# axiom_beta_plugin_module_TE0714_SDI_v0_4.net
KiCad netlist of a schematic drawn in EAGLE
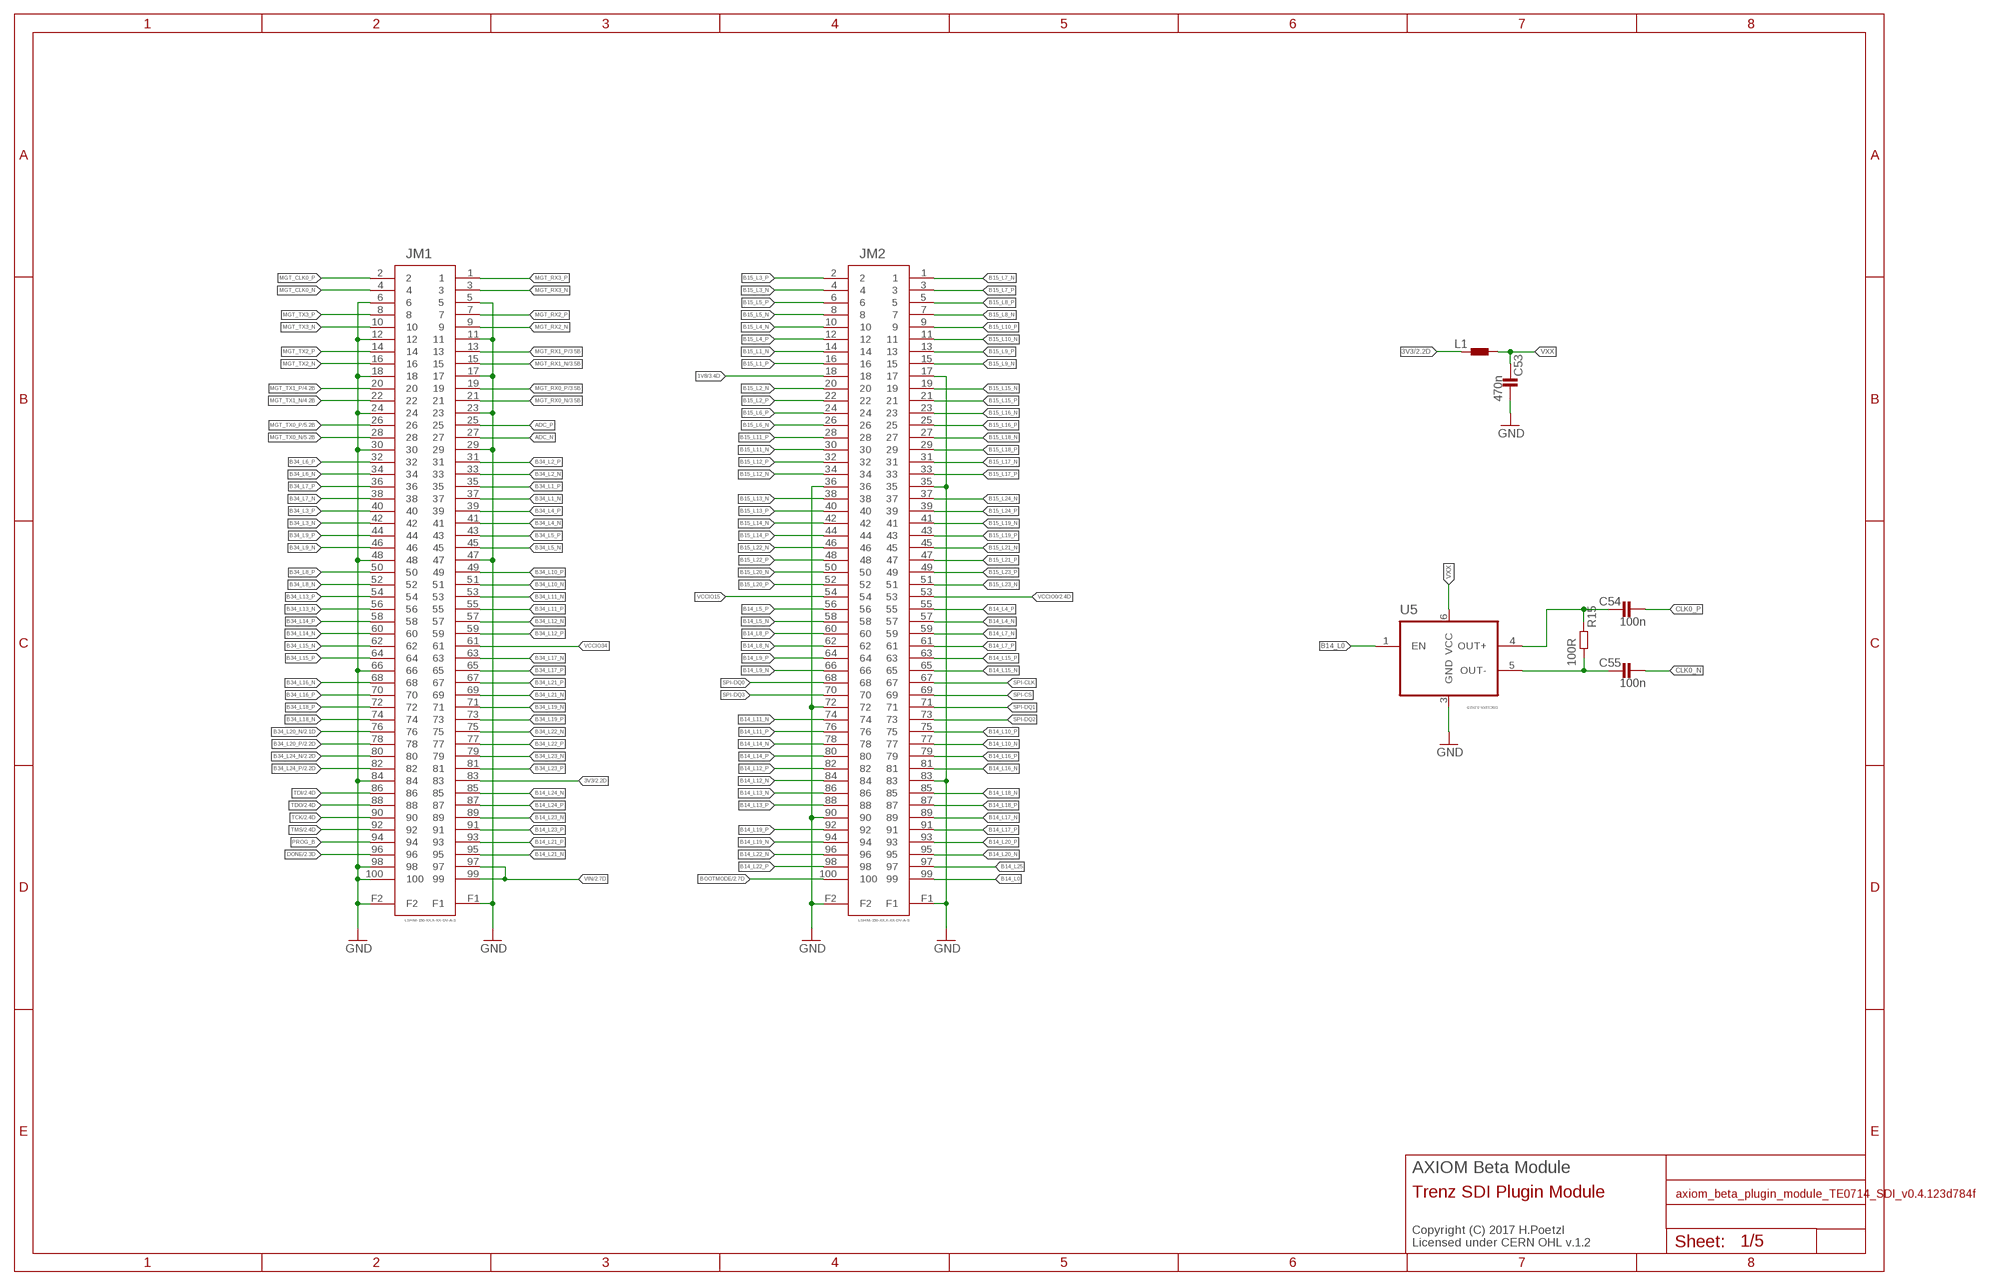
[diagram p0: schematic, sheet 1]
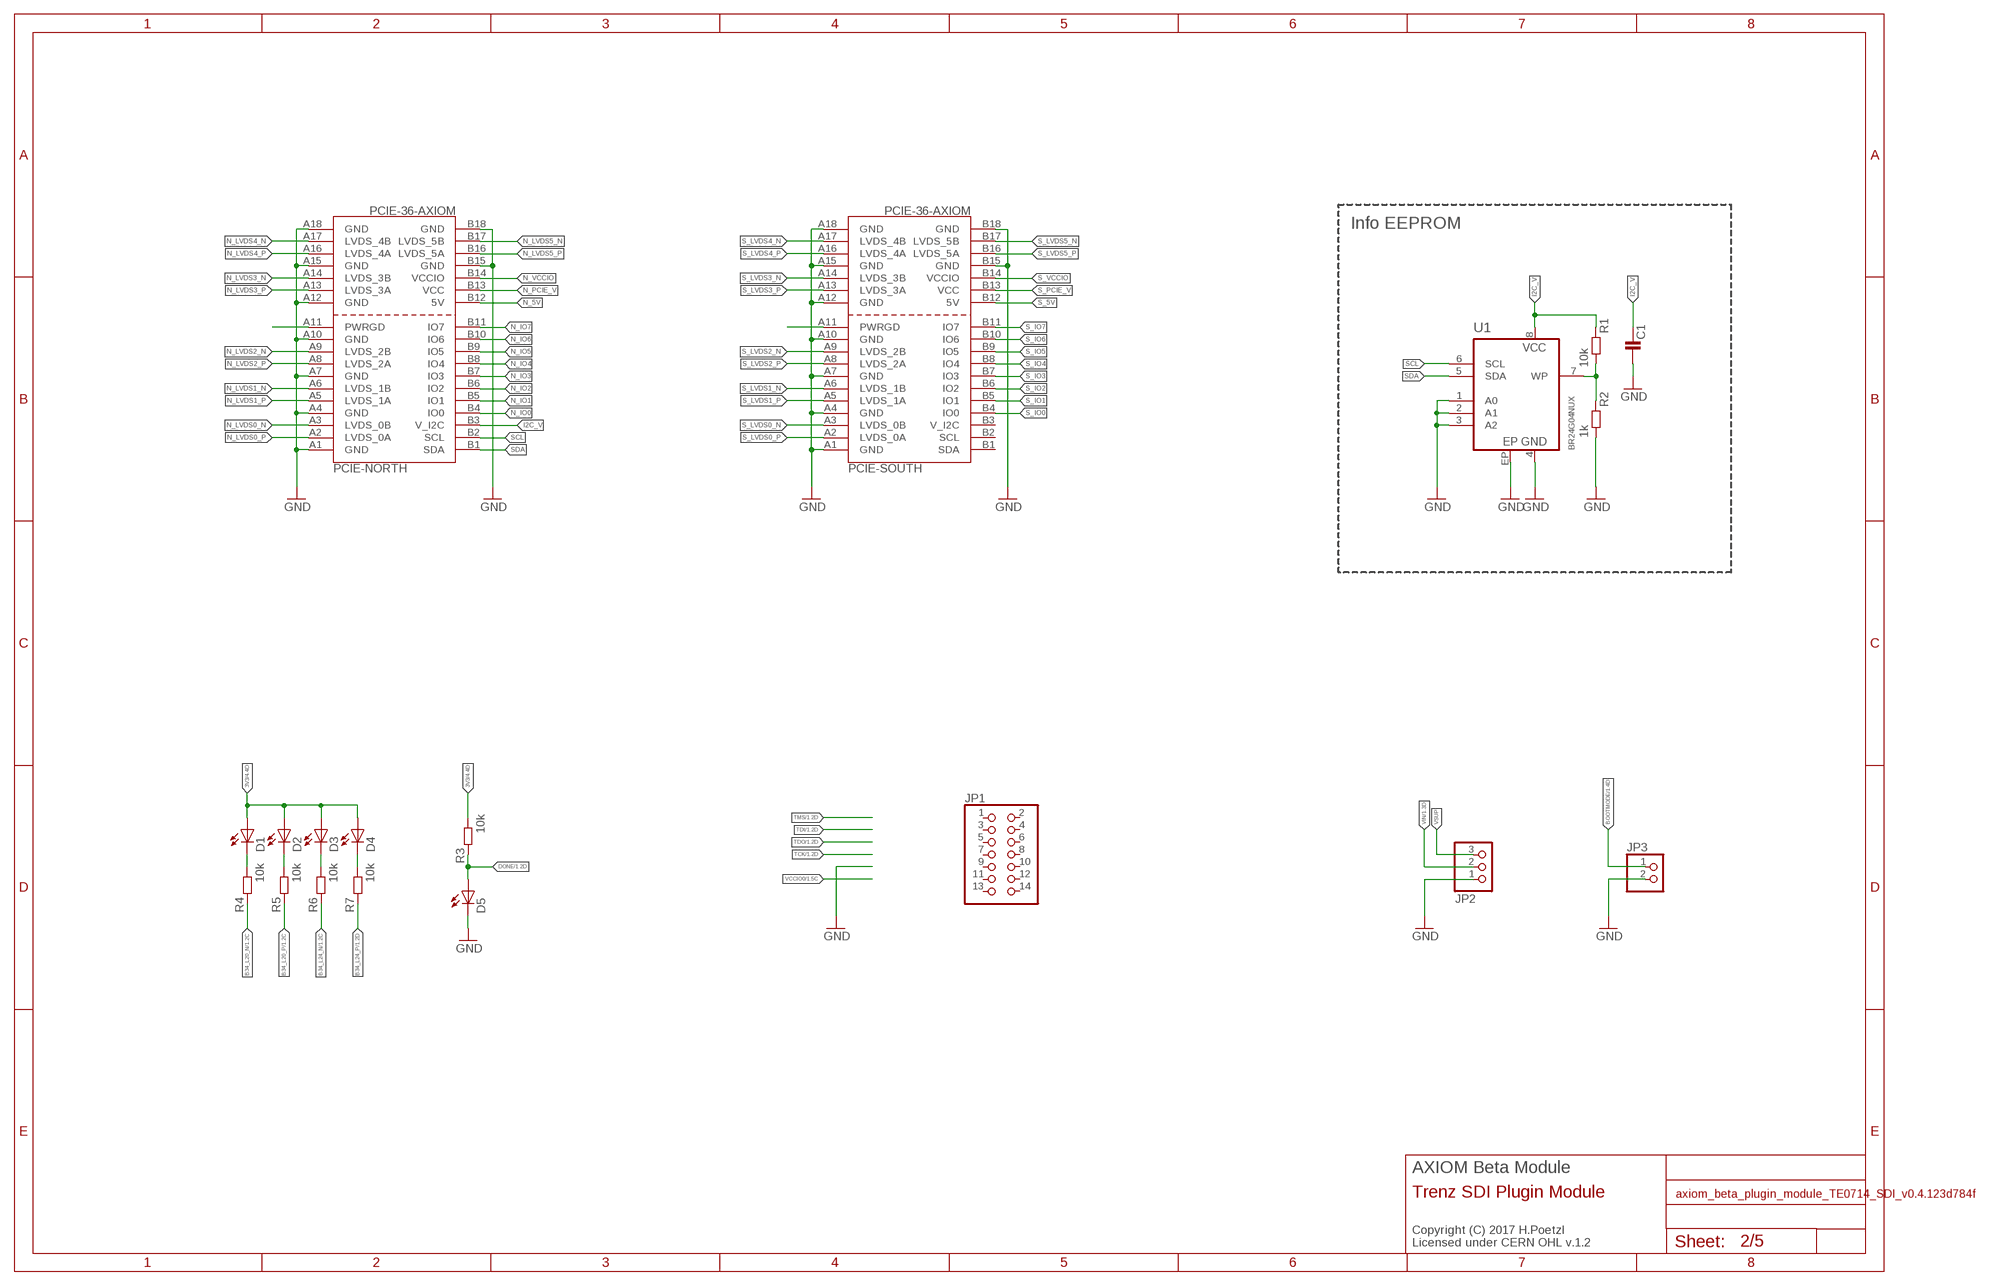
[diagram p1: schematic, sheet 2]
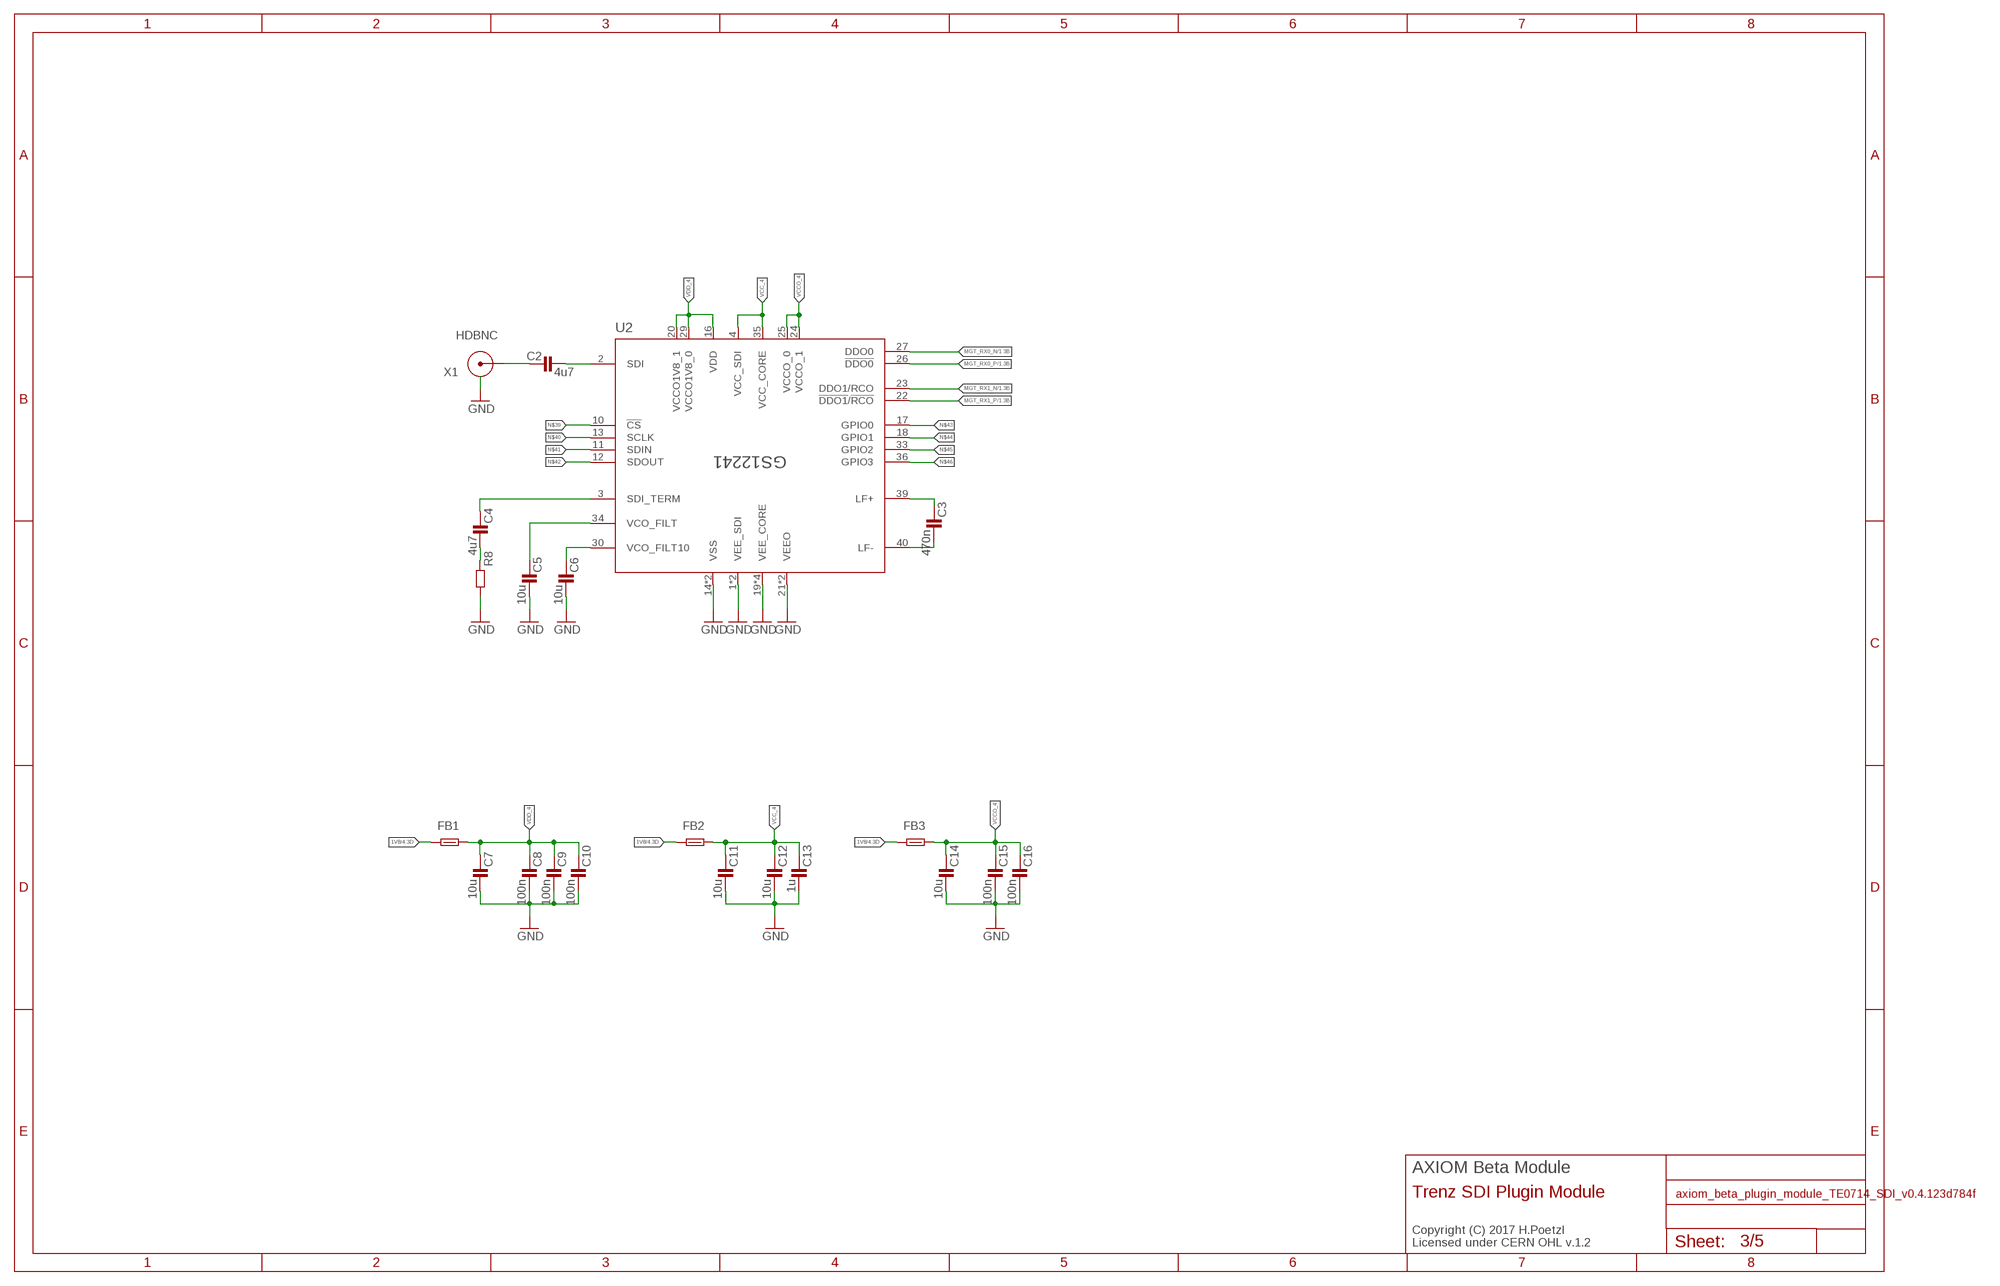
[diagram p2: schematic, sheet 3]
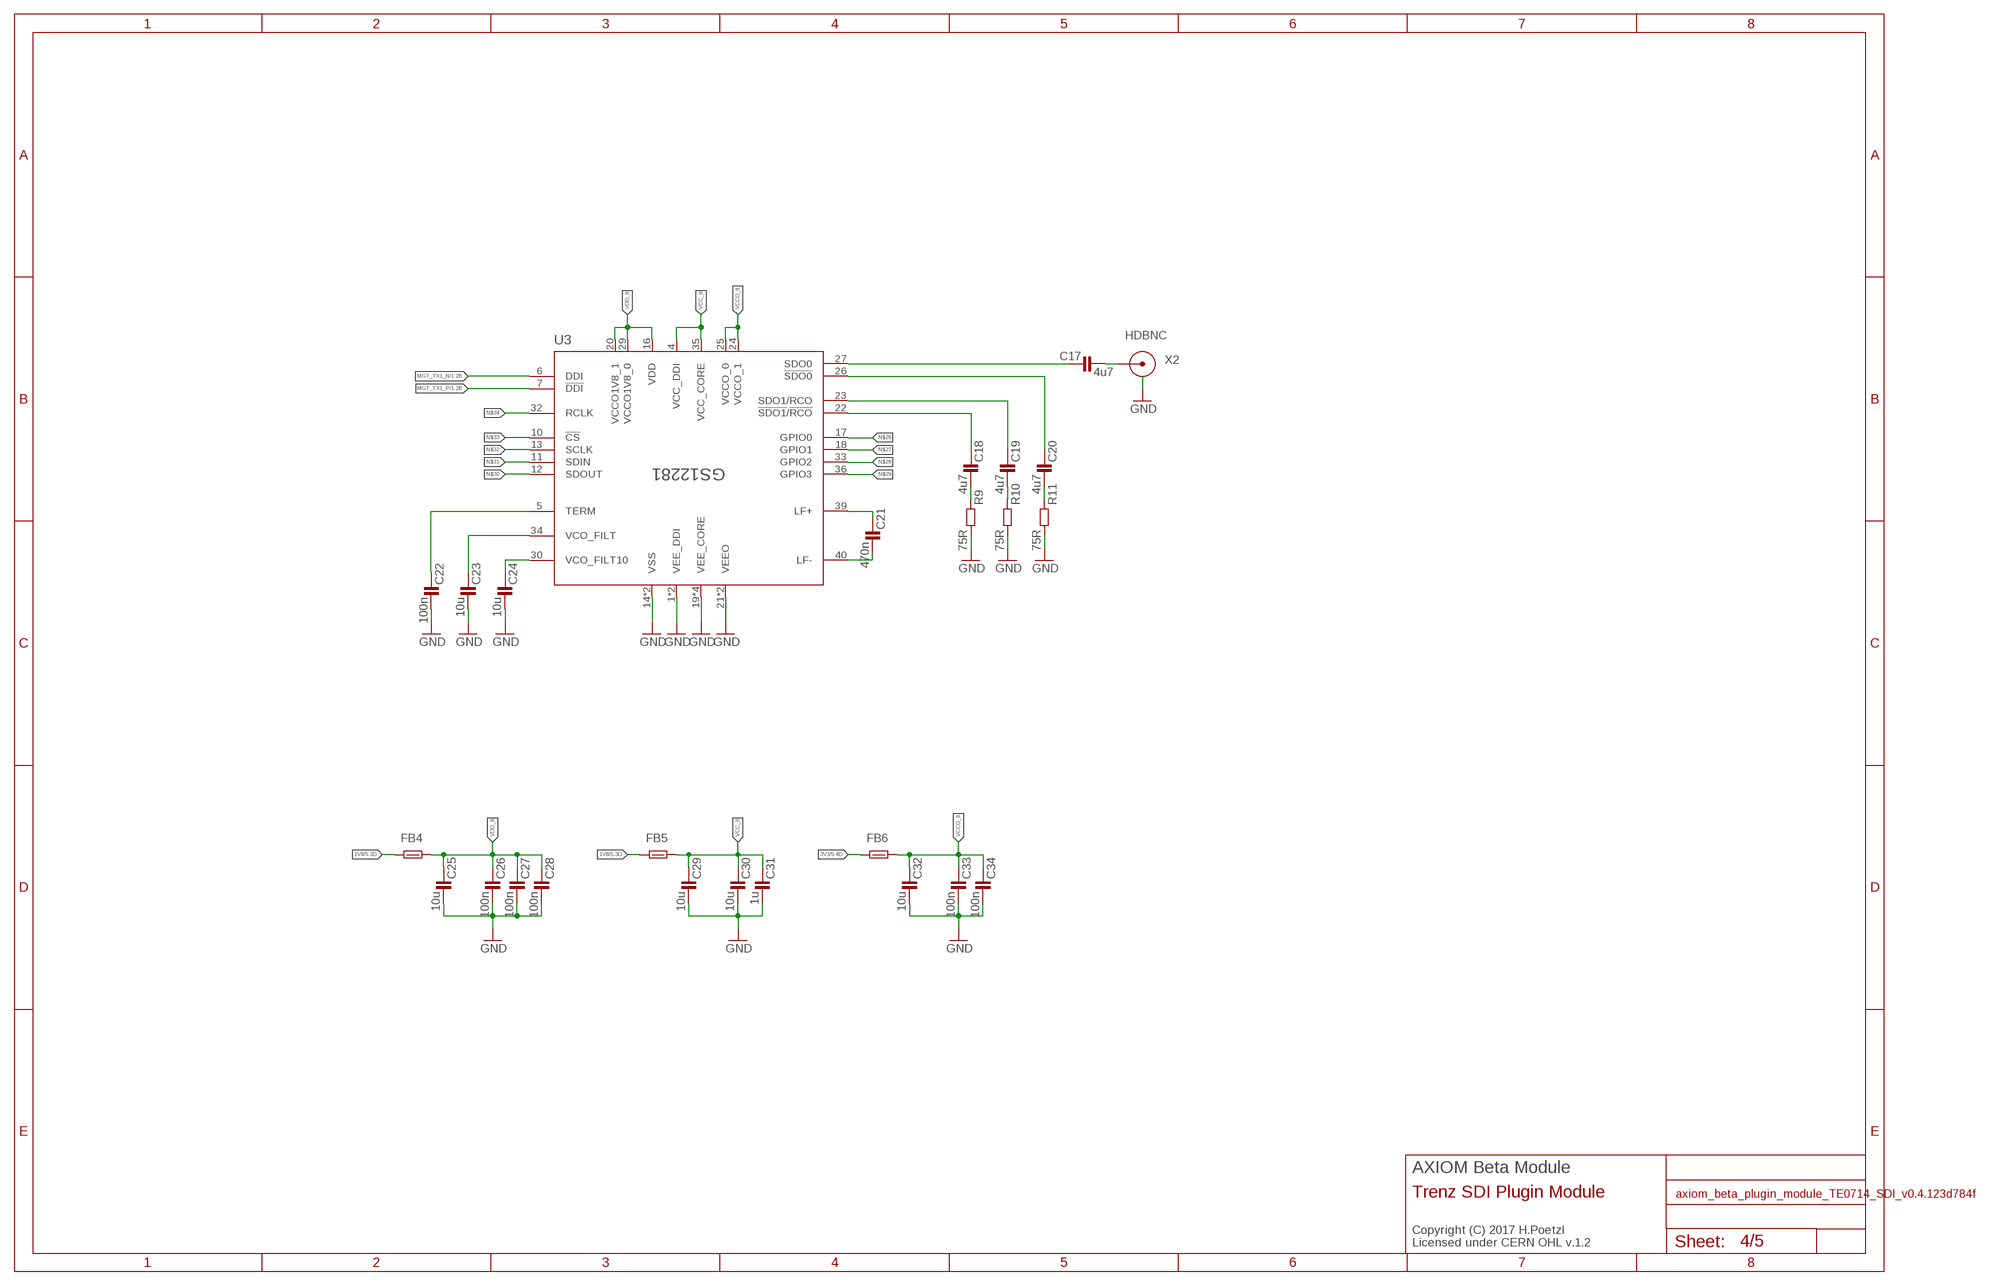
[diagram p3: schematic, sheet 4]
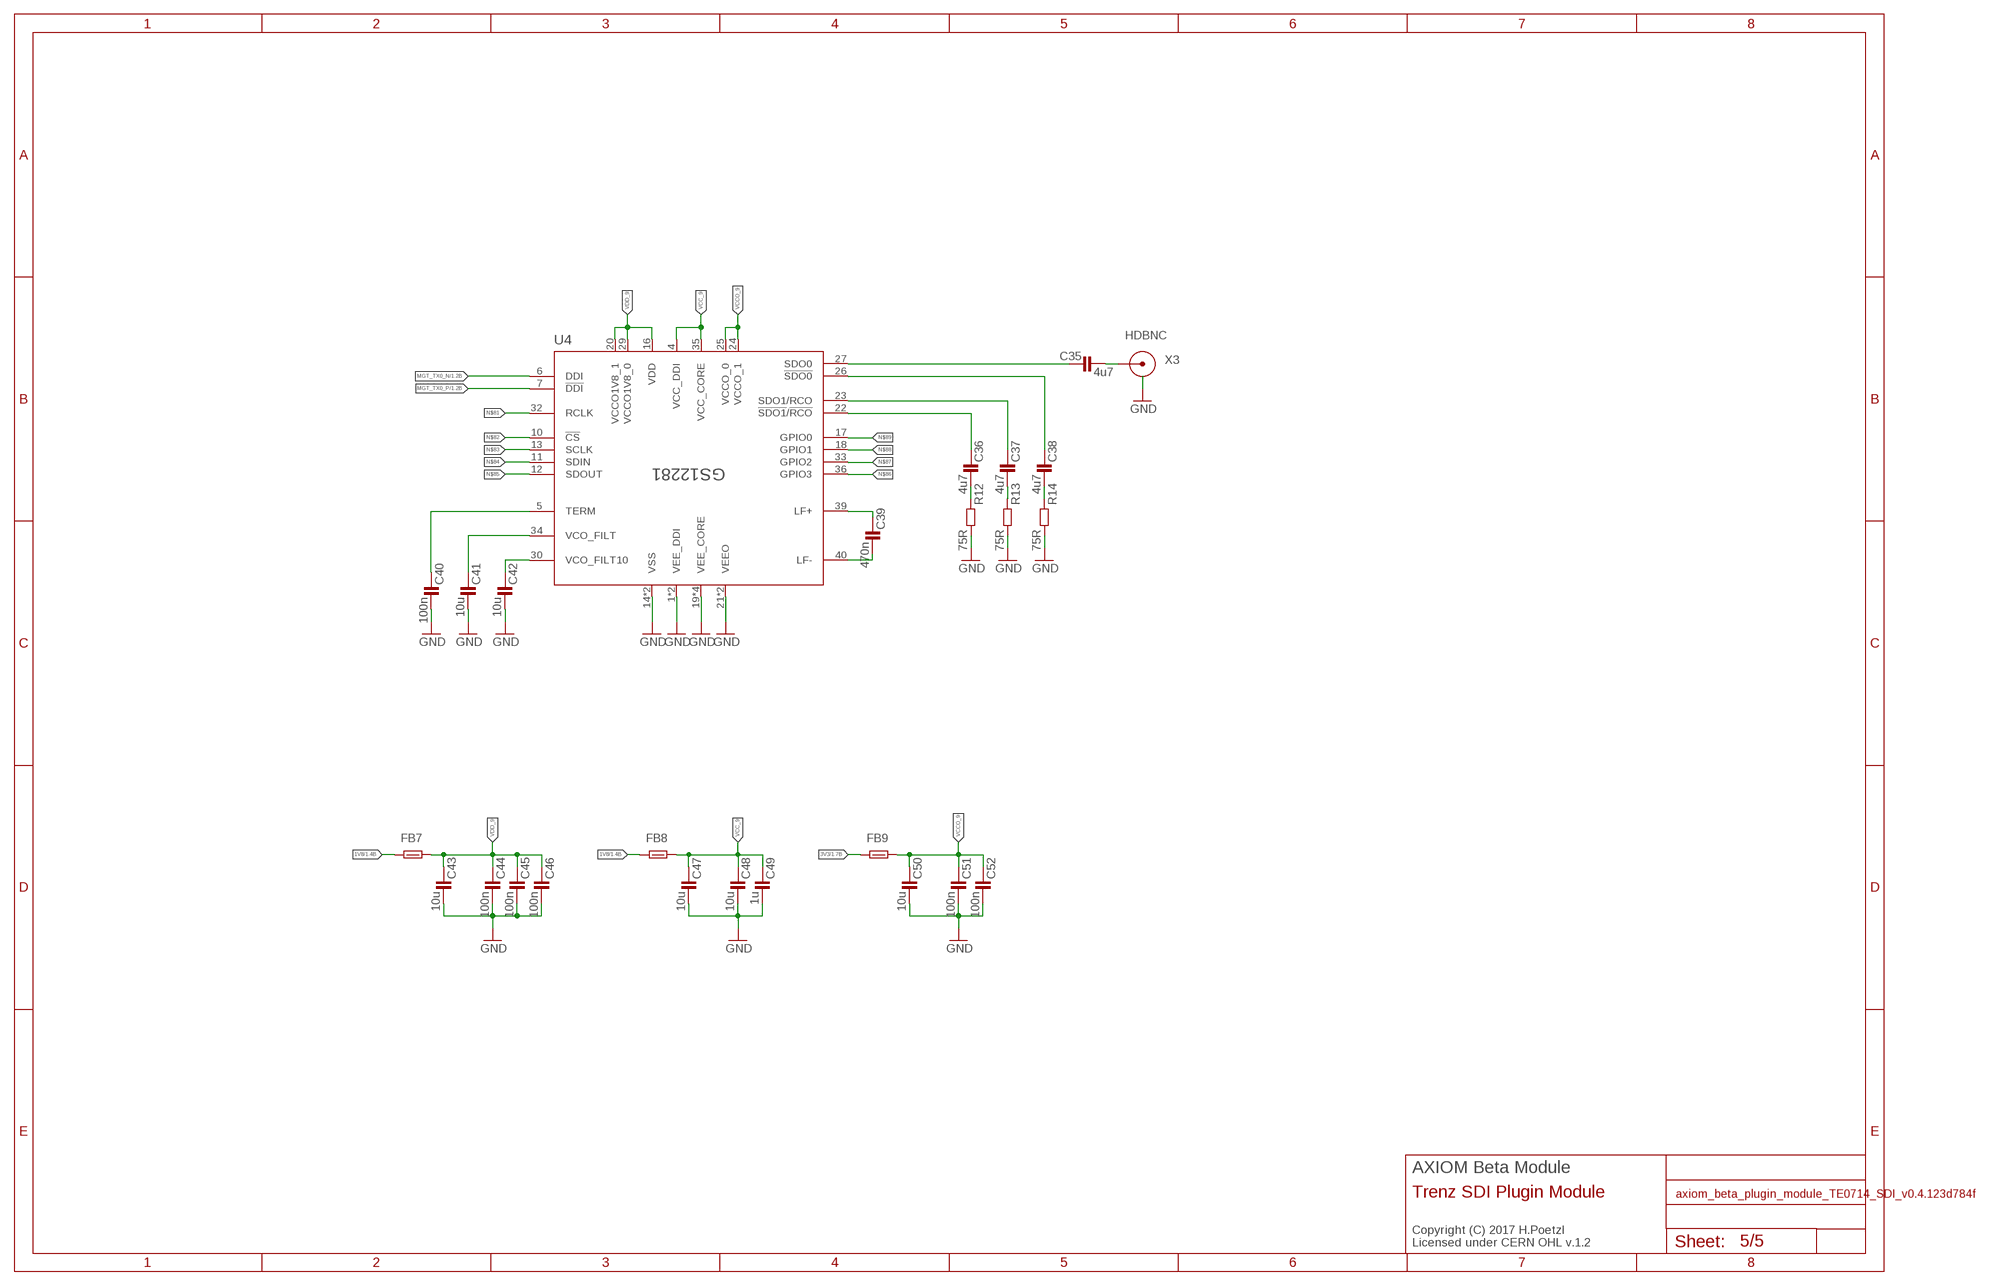
[diagram p4: schematic, sheet 5]

(export (version "E")
  (design (tool "Eeschema 10.0.6"))
  (components
    (comp (ref "C17")
      (value "4u7")
      (footprint "eagle-import:0402-C")
      (libsource (lib "eagle-import") (part "C0402-C"))
    )
    (comp (ref "C18")
      (value "4u7")
      (footprint "eagle-import:0201-C")
      (libsource (lib "eagle-import") (part "C0201-C"))
    )
    (comp (ref "C19")
      (value "4u7")
      (footprint "eagle-import:0201-C")
      (libsource (lib "eagle-import") (part "C0201-C"))
    )
    (comp (ref "C20")
      (value "4u7")
      (footprint "eagle-import:0201-C")
      (libsource (lib "eagle-import") (part "C0201-C"))
    )
    (comp (ref "C21")
      (value "470n")
      (footprint "eagle-import:0201-C")
      (libsource (lib "eagle-import") (part "C0201-C"))
    )
    (comp (ref "C22")
      (value "100n")
      (footprint "eagle-import:0201-C")
      (libsource (lib "eagle-import") (part "C0201-C"))
    )
    (comp (ref "C23")
      (value "10u")
      (footprint "eagle-import:0201-C")
      (libsource (lib "eagle-import") (part "C0201-C"))
    )
    (comp (ref "C24")
      (value "10u")
      (footprint "eagle-import:0201-C")
      (libsource (lib "eagle-import") (part "C0201-C"))
    )
    (comp (ref "C25")
      (value "10u")
      (footprint "eagle-import:0402-C")
      (libsource (lib "eagle-import") (part "C0402-C"))
    )
    (comp (ref "C26")
      (value "100n")
      (footprint "eagle-import:0201-C")
      (libsource (lib "eagle-import") (part "C0201-C"))
    )
    (comp (ref "C27")
      (value "100n")
      (footprint "eagle-import:0201-C")
      (libsource (lib "eagle-import") (part "C0201-C"))
    )
    (comp (ref "C28")
      (value "100n")
      (footprint "eagle-import:0201-C")
      (libsource (lib "eagle-import") (part "C0201-C"))
    )
    (comp (ref "C29")
      (value "10u")
      (footprint "eagle-import:0402-C")
      (libsource (lib "eagle-import") (part "C0402-C"))
    )
    (comp (ref "C30")
      (value "10u")
      (footprint "eagle-import:0201-C")
      (libsource (lib "eagle-import") (part "C0201-C"))
    )
    (comp (ref "C31")
      (value "1u")
      (footprint "eagle-import:0201-C")
      (libsource (lib "eagle-import") (part "C0201-C"))
    )
    (comp (ref "C32")
      (value "10u")
      (footprint "eagle-import:0402-C")
      (libsource (lib "eagle-import") (part "C0402-C"))
    )
    (comp (ref "C33")
      (value "100n")
      (footprint "eagle-import:0201-C")
      (libsource (lib "eagle-import") (part "C0201-C"))
    )
    (comp (ref "C34")
      (value "100n")
      (footprint "eagle-import:0201-C")
      (libsource (lib "eagle-import") (part "C0201-C"))
    )
    (comp (ref "FB4")
      (value "FB0402-C")
      (footprint "eagle-import:0402-C")
      (libsource (lib "eagle-import") (part "FB0402-C"))
    )
    (comp (ref "FB5")
      (value "FB0402-C")
      (footprint "eagle-import:0402-C")
      (libsource (lib "eagle-import") (part "FB0402-C"))
    )
    (comp (ref "FB6")
      (value "FB0402-C")
      (footprint "eagle-import:0402-C")
      (libsource (lib "eagle-import") (part "FB0402-C"))
    )
    (comp (ref "R9")
      (value "75R")
      (footprint "eagle-import:0201-C")
      (libsource (lib "eagle-import") (part "R0201-C"))
    )
    (comp (ref "R10")
      (value "75R")
      (footprint "eagle-import:0201-C")
      (libsource (lib "eagle-import") (part "R0201-C"))
    )
    (comp (ref "R11")
      (value "75R")
      (footprint "eagle-import:0201-C")
      (libsource (lib "eagle-import") (part "R0201-C"))
    )
    (comp (ref "U3")
      (value "GS12281")
      (footprint "eagle-import:UQFN40P600X400X100-41N")
      (libsource (lib "eagle-import") (part "GS12281"))
    )
    (comp (ref "X2")
      (value "HDBNC")
      (footprint "eagle-import:HDBNC_EDGE_2SIDE")
      (libsource (lib "eagle-import") (part "HDBNC"))
    )
    (comp (ref "C1")
      (value "C0402-B")
      (footprint "eagle-import:0402-B")
      (libsource (lib "eagle-import") (part "C0402-B"))
    )
    (comp (ref "D1")
      (value "LED")
      (footprint "eagle-import:SMARTLED-TTW")
      (libsource (lib "eagle-import") (part "LED"))
    )
    (comp (ref "D2")
      (value "LED")
      (footprint "eagle-import:SMARTLED-TTW")
      (libsource (lib "eagle-import") (part "LED"))
    )
    (comp (ref "D3")
      (value "LED")
      (footprint "eagle-import:SMARTLED-TTW")
      (libsource (lib "eagle-import") (part "LED"))
    )
    (comp (ref "D4")
      (value "LED")
      (footprint "eagle-import:SMARTLED-TTW")
      (libsource (lib "eagle-import") (part "LED"))
    )
    (comp (ref "D5")
      (value "LED")
      (footprint "eagle-import:SMARTLED-TTW")
      (libsource (lib "eagle-import") (part "LED"))
    )
    (comp (ref "JP1")
      (value "PINHD-2X07_2.00")
      (footprint "eagle-import:2X07M")
      (libsource (lib "eagle-import") (part "PINHD-2X07_2.00"))
    )
    (comp (ref "JP2")
      (value "PINHD-1X03_2.54-90°-S")
      (footprint "eagle-import:1X03_90-S")
      (libsource (lib "eagle-import") (part "PINHD-1X03_2.54-90°-S"))
    )
    (comp (ref "JP3")
      (value "PINHD-1X02_2.54-S")
      (footprint "eagle-import:1X02-S")
      (libsource (lib "eagle-import") (part "PINHD-1X02_2.54-S"))
    )
    (comp (ref "PCIE-NORTH")
      (value "PCIE-36-AXIOM")
      (footprint "eagle-import:PCIE-36-AXIOM")
      (libsource (lib "eagle-import") (part "PCIE-36-AXIOM"))
    )
    (comp (ref "PCIE-SOUTH")
      (value "PCIE-36-AXIOM")
      (footprint "eagle-import:PCIE-36-AXIOM")
      (libsource (lib "eagle-import") (part "PCIE-36-AXIOM"))
    )
    (comp (ref "R1")
      (value "10k")
      (footprint "eagle-import:0402-B")
      (libsource (lib "eagle-import") (part "R0402-B"))
    )
    (comp (ref "R2")
      (value "1k")
      (footprint "eagle-import:0402-B")
      (libsource (lib "eagle-import") (part "R0402-B"))
    )
    (comp (ref "R3")
      (value "10k")
      (footprint "eagle-import:0402-C")
      (libsource (lib "eagle-import") (part "R0402-C"))
    )
    (comp (ref "R4")
      (value "10k")
      (footprint "eagle-import:0402-C")
      (libsource (lib "eagle-import") (part "R0402-C"))
    )
    (comp (ref "R5")
      (value "10k")
      (footprint "eagle-import:0402-C")
      (libsource (lib "eagle-import") (part "R0402-C"))
    )
    (comp (ref "R6")
      (value "10k")
      (footprint "eagle-import:0402-C")
      (libsource (lib "eagle-import") (part "R0402-C"))
    )
    (comp (ref "R7")
      (value "10k")
      (footprint "eagle-import:0402-C")
      (libsource (lib "eagle-import") (part "R0402-C"))
    )
    (comp (ref "U1")
      (value "BR24G04NUX")
      (footprint "eagle-import:DFN200X300X100-9N")
      (libsource (lib "eagle-import") (part "BR24G04NUX"))
    )
    (comp (ref "C35")
      (value "4u7")
      (footprint "eagle-import:0402-C")
      (libsource (lib "eagle-import") (part "C0402-C"))
    )
    (comp (ref "C36")
      (value "4u7")
      (footprint "eagle-import:0201-C")
      (libsource (lib "eagle-import") (part "C0201-C"))
    )
    (comp (ref "C37")
      (value "4u7")
      (footprint "eagle-import:0201-C")
      (libsource (lib "eagle-import") (part "C0201-C"))
    )
    (comp (ref "C38")
      (value "4u7")
      (footprint "eagle-import:0201-C")
      (libsource (lib "eagle-import") (part "C0201-C"))
    )
    (comp (ref "C39")
      (value "470n")
      (footprint "eagle-import:0201-C")
      (libsource (lib "eagle-import") (part "C0201-C"))
    )
    (comp (ref "C40")
      (value "100n")
      (footprint "eagle-import:0201-C")
      (libsource (lib "eagle-import") (part "C0201-C"))
    )
    (comp (ref "C41")
      (value "10u")
      (footprint "eagle-import:0201-C")
      (libsource (lib "eagle-import") (part "C0201-C"))
    )
    (comp (ref "C42")
      (value "10u")
      (footprint "eagle-import:0201-C")
      (libsource (lib "eagle-import") (part "C0201-C"))
    )
    (comp (ref "C43")
      (value "10u")
      (footprint "eagle-import:0402-C")
      (libsource (lib "eagle-import") (part "C0402-C"))
    )
    (comp (ref "C44")
      (value "100n")
      (footprint "eagle-import:0201-C")
      (libsource (lib "eagle-import") (part "C0201-C"))
    )
    (comp (ref "C45")
      (value "100n")
      (footprint "eagle-import:0201-C")
      (libsource (lib "eagle-import") (part "C0201-C"))
    )
    (comp (ref "C46")
      (value "100n")
      (footprint "eagle-import:0201-C")
      (libsource (lib "eagle-import") (part "C0201-C"))
    )
    (comp (ref "C47")
      (value "10u")
      (footprint "eagle-import:0402-C")
      (libsource (lib "eagle-import") (part "C0402-C"))
    )
    (comp (ref "C48")
      (value "10u")
      (footprint "eagle-import:0201-C")
      (libsource (lib "eagle-import") (part "C0201-C"))
    )
    (comp (ref "C49")
      (value "1u")
      (footprint "eagle-import:0201-C")
      (libsource (lib "eagle-import") (part "C0201-C"))
    )
    (comp (ref "C50")
      (value "10u")
      (footprint "eagle-import:0402-C")
      (libsource (lib "eagle-import") (part "C0402-C"))
    )
    (comp (ref "C51")
      (value "100n")
      (footprint "eagle-import:0201-C")
      (libsource (lib "eagle-import") (part "C0201-C"))
    )
    (comp (ref "C52")
      (value "100n")
      (footprint "eagle-import:0201-C")
      (libsource (lib "eagle-import") (part "C0201-C"))
    )
    (comp (ref "FB7")
      (value "FB0402-C")
      (footprint "eagle-import:0402-C")
      (libsource (lib "eagle-import") (part "FB0402-C"))
    )
    (comp (ref "FB8")
      (value "FB0402-C")
      (footprint "eagle-import:0402-C")
      (libsource (lib "eagle-import") (part "FB0402-C"))
    )
    (comp (ref "FB9")
      (value "FB0402-C")
      (footprint "eagle-import:0402-C")
      (libsource (lib "eagle-import") (part "FB0402-C"))
    )
    (comp (ref "R12")
      (value "75R")
      (footprint "eagle-import:0201-C")
      (libsource (lib "eagle-import") (part "R0201-C"))
    )
    (comp (ref "R13")
      (value "75R")
      (footprint "eagle-import:0201-C")
      (libsource (lib "eagle-import") (part "R0201-C"))
    )
    (comp (ref "R14")
      (value "75R")
      (footprint "eagle-import:0201-C")
      (libsource (lib "eagle-import") (part "R0201-C"))
    )
    (comp (ref "U4")
      (value "GS12281")
      (footprint "eagle-import:UQFN40P600X400X100-41N")
      (libsource (lib "eagle-import") (part "GS12281"))
    )
    (comp (ref "X3")
      (value "HDBNC")
      (footprint "eagle-import:HDBNC_EDGE_2SIDE")
      (libsource (lib "eagle-import") (part "HDBNC"))
    )
    (comp (ref "C53")
      (value "470n")
      (footprint "eagle-import:0402-C")
      (libsource (lib "eagle-import") (part "C0402-C"))
    )
    (comp (ref "C54")
      (value "100n")
      (footprint "eagle-import:0201-C")
      (libsource (lib "eagle-import") (part "C0201-C"))
    )
    (comp (ref "C55")
      (value "100n")
      (footprint "eagle-import:0201-C")
      (libsource (lib "eagle-import") (part "C0201-C"))
    )
    (comp (ref "JM1")
      (value "LSHM-150-XX.X-XX-DV-A-S")
      (footprint "eagle-import:LSHM-150-XX.X-XX-DV-A-S")
      (libsource (lib "eagle-import") (part "LSHM-150-XX.X-XX-DV-A-S"))
    )
    (comp (ref "JM2")
      (value "LSHM-150-XX.X-XX-DV-A-S")
      (footprint "eagle-import:LSHM-150-XX.X-XX-DV-A-S")
      (libsource (lib "eagle-import") (part "LSHM-150-XX.X-XX-DV-A-S"))
    )
    (comp (ref "L1")
      (value "L0402-C")
      (footprint "eagle-import:0402-C")
      (libsource (lib "eagle-import") (part "L0402-C"))
    )
    (comp (ref "R15")
      (value "100R")
      (footprint "eagle-import:0201-C")
      (libsource (lib "eagle-import") (part "R0201-C"))
    )
    (comp (ref "U5")
      (value "DSC11XX-3.2X2.5")
      (footprint "eagle-import:3.2X2.5")
      (libsource (lib "eagle-import") (part "DSC11XX-3.2X2.5"))
    )
    (comp (ref "C2")
      (value "4u7")
      (footprint "eagle-import:0402-C")
      (libsource (lib "eagle-import") (part "C0402-C"))
    )
    (comp (ref "C3")
      (value "470n")
      (footprint "eagle-import:0201-C")
      (libsource (lib "eagle-import") (part "C0201-C"))
    )
    (comp (ref "C4")
      (value "4u7")
      (footprint "eagle-import:0201-C")
      (libsource (lib "eagle-import") (part "C0201-C"))
    )
    (comp (ref "C5")
      (value "10u")
      (footprint "eagle-import:0201-C")
      (libsource (lib "eagle-import") (part "C0201-C"))
    )
    (comp (ref "C6")
      (value "10u")
      (footprint "eagle-import:0201-C")
      (libsource (lib "eagle-import") (part "C0201-C"))
    )
    (comp (ref "C7")
      (value "10u")
      (footprint "eagle-import:0402-C")
      (libsource (lib "eagle-import") (part "C0402-C"))
    )
    (comp (ref "C8")
      (value "100n")
      (footprint "eagle-import:0201-C")
      (libsource (lib "eagle-import") (part "C0201-C"))
    )
    (comp (ref "C9")
      (value "100n")
      (footprint "eagle-import:0201-C")
      (libsource (lib "eagle-import") (part "C0201-C"))
    )
    (comp (ref "C10")
      (value "100n")
      (footprint "eagle-import:0201-C")
      (libsource (lib "eagle-import") (part "C0201-C"))
    )
    (comp (ref "C11")
      (value "10u")
      (footprint "eagle-import:0402-C")
      (libsource (lib "eagle-import") (part "C0402-C"))
    )
    (comp (ref "C12")
      (value "10u")
      (footprint "eagle-import:0201-C")
      (libsource (lib "eagle-import") (part "C0201-C"))
    )
    (comp (ref "C13")
      (value "1u")
      (footprint "eagle-import:0201-C")
      (libsource (lib "eagle-import") (part "C0201-C"))
    )
    (comp (ref "C14")
      (value "10u")
      (footprint "eagle-import:0402-C")
      (libsource (lib "eagle-import") (part "C0402-C"))
    )
    (comp (ref "C15")
      (value "100n")
      (footprint "eagle-import:0201-C")
      (libsource (lib "eagle-import") (part "C0201-C"))
    )
    (comp (ref "C16")
      (value "100n")
      (footprint "eagle-import:0201-C")
      (libsource (lib "eagle-import") (part "C0201-C"))
    )
    (comp (ref "FB1")
      (value "FB0402-C")
      (footprint "eagle-import:0402-C")
      (libsource (lib "eagle-import") (part "FB0402-C"))
    )
    (comp (ref "FB2")
      (value "FB0402-C")
      (footprint "eagle-import:0402-C")
      (libsource (lib "eagle-import") (part "FB0402-C"))
    )
    (comp (ref "FB3")
      (value "FB0402-C")
      (footprint "eagle-import:0402-C")
      (libsource (lib "eagle-import") (part "FB0402-C"))
    )
    (comp (ref "R8")
      (value "R0201-C")
      (footprint "eagle-import:0201-C")
      (libsource (lib "eagle-import") (part "R0201-C"))
    )
    (comp (ref "U2")
      (value "GS12241")
      (footprint "eagle-import:UQFN40P600X400X100-41N")
      (libsource (lib "eagle-import") (part "GS12241"))
    )
    (comp (ref "X1")
      (value "HDBNC")
      (footprint "eagle-import:HDBNC_EDGE_2SIDE")
      (libsource (lib "eagle-import") (part "HDBNC"))
    )
  )
  (nets
    (net (code "1") (name "1V8") (class "Default")
      (node (ref "FB1") (pin "1") (pinfunction "1_1") (pintype "passive"))
      (node (ref "FB2") (pin "1") (pinfunction "1_1") (pintype "passive"))
      (node (ref "FB3") (pin "1") (pinfunction "1_1") (pintype "passive"))
      (node (ref "FB4") (pin "1") (pinfunction "1_1") (pintype "passive"))
      (node (ref "FB5") (pin "1") (pinfunction "1_1") (pintype "passive"))
      (node (ref "FB7") (pin "1") (pinfunction "1_1") (pintype "passive"))
      (node (ref "FB8") (pin "1") (pinfunction "1_1") (pintype "passive"))
      (node (ref "JM2") (pin "18") (pinfunction "18_18") (pintype "bidirectional"))
    )
    (net (code "2") (name "3V3") (class "Default")
      (node (ref "D1") (pin "A@1") (pinfunction "A_A@1") (pintype "passive"))
      (node (ref "D2") (pin "A@1") (pinfunction "A_A@1") (pintype "passive"))
      (node (ref "D3") (pin "A@1") (pinfunction "A_A@1") (pintype "passive"))
      (node (ref "D4") (pin "A@1") (pinfunction "A_A@1") (pintype "passive"))
      (node (ref "FB6") (pin "1") (pinfunction "1_1") (pintype "passive"))
      (node (ref "FB9") (pin "1") (pinfunction "1_1") (pintype "passive"))
      (node (ref "JM1") (pin "83") (pinfunction "83_83") (pintype "bidirectional"))
      (node (ref "L1") (pin "1") (pinfunction "1_1") (pintype "passive"))
      (node (ref "R3") (pin "2") (pinfunction "2_2") (pintype "passive"))
    )
    (net (code "3") (name "ADC_N") (class "Default")
      (node (ref "JM1") (pin "27") (pinfunction "27_27") (pintype "bidirectional"))
    )
    (net (code "4") (name "ADC_P") (class "Default")
      (node (ref "JM1") (pin "25") (pinfunction "25_25") (pintype "bidirectional"))
    )
    (net (code "5") (name "B14_L0") (class "Default")
      (node (ref "JM2") (pin "99") (pinfunction "99_99") (pintype "bidirectional"))
      (node (ref "U5") (pin "1") (pinfunction "EN_1") (pintype "input"))
    )
    (net (code "6") (name "B14_L4_N") (class "Default")
      (node (ref "JM2") (pin "57") (pinfunction "57_57") (pintype "bidirectional"))
    )
    (net (code "7") (name "B14_L4_P") (class "Default")
      (node (ref "JM2") (pin "55") (pinfunction "55_55") (pintype "bidirectional"))
    )
    (net (code "8") (name "B14_L5_N") (class "Default")
      (node (ref "JM2") (pin "58") (pinfunction "58_58") (pintype "bidirectional"))
    )
    (net (code "9") (name "B14_L5_P") (class "Default")
      (node (ref "JM2") (pin "56") (pinfunction "56_56") (pintype "bidirectional"))
    )
    (net (code "10") (name "B14_L7_N") (class "Default")
      (node (ref "JM2") (pin "59") (pinfunction "59_59") (pintype "bidirectional"))
    )
    (net (code "11") (name "B14_L7_P") (class "Default")
      (node (ref "JM2") (pin "61") (pinfunction "61_61") (pintype "bidirectional"))
    )
    (net (code "12") (name "B14_L8_N") (class "Default")
      (node (ref "JM2") (pin "62") (pinfunction "62_62") (pintype "bidirectional"))
    )
    (net (code "13") (name "B14_L8_P") (class "Default")
      (node (ref "JM2") (pin "60") (pinfunction "60_60") (pintype "bidirectional"))
    )
    (net (code "14") (name "B14_L9_N") (class "Default")
      (node (ref "JM2") (pin "66") (pinfunction "66_66") (pintype "bidirectional"))
    )
    (net (code "15") (name "B14_L9_P") (class "Default")
      (node (ref "JM2") (pin "64") (pinfunction "64_64") (pintype "bidirectional"))
    )
    (net (code "16") (name "B14_L10_N") (class "Default")
      (node (ref "JM2") (pin "77") (pinfunction "77_77") (pintype "bidirectional"))
    )
    (net (code "17") (name "B14_L10_P") (class "Default")
      (node (ref "JM2") (pin "75") (pinfunction "75_75") (pintype "bidirectional"))
    )
    (net (code "18") (name "B14_L11_N") (class "Default")
      (node (ref "JM2") (pin "74") (pinfunction "74_74") (pintype "bidirectional"))
    )
    (net (code "19") (name "B14_L11_P") (class "Default")
      (node (ref "JM2") (pin "76") (pinfunction "76_76") (pintype "bidirectional"))
    )
    (net (code "20") (name "B14_L12_N") (class "Default")
      (node (ref "JM2") (pin "84") (pinfunction "84_84") (pintype "bidirectional"))
    )
    (net (code "21") (name "B14_L12_P") (class "Default")
      (node (ref "JM2") (pin "82") (pinfunction "82_82") (pintype "bidirectional"))
    )
    (net (code "22") (name "B14_L13_N") (class "Default")
      (node (ref "JM2") (pin "86") (pinfunction "86_86") (pintype "bidirectional"))
    )
    (net (code "23") (name "B14_L13_P") (class "Default")
      (node (ref "JM2") (pin "88") (pinfunction "88_88") (pintype "bidirectional"))
    )
    (net (code "24") (name "B14_L14_N") (class "Default")
      (node (ref "JM2") (pin "78") (pinfunction "78_78") (pintype "bidirectional"))
    )
    (net (code "25") (name "B14_L14_P") (class "Default")
      (node (ref "JM2") (pin "80") (pinfunction "80_80") (pintype "bidirectional"))
    )
    (net (code "26") (name "B14_L15_N") (class "Default")
      (node (ref "JM2") (pin "65") (pinfunction "65_65") (pintype "bidirectional"))
    )
    (net (code "27") (name "B14_L15_P") (class "Default")
      (node (ref "JM2") (pin "63") (pinfunction "63_63") (pintype "bidirectional"))
    )
    (net (code "28") (name "B14_L16_N") (class "Default")
      (node (ref "JM2") (pin "81") (pinfunction "81_81") (pintype "bidirectional"))
    )
    (net (code "29") (name "B14_L16_P") (class "Default")
      (node (ref "JM2") (pin "79") (pinfunction "79_79") (pintype "bidirectional"))
    )
    (net (code "30") (name "B14_L17_N") (class "Default")
      (node (ref "JM2") (pin "89") (pinfunction "89_89") (pintype "bidirectional"))
    )
    (net (code "31") (name "B14_L17_P") (class "Default")
      (node (ref "JM2") (pin "91") (pinfunction "91_91") (pintype "bidirectional"))
    )
    (net (code "32") (name "B14_L18_N") (class "Default")
      (node (ref "JM2") (pin "85") (pinfunction "85_85") (pintype "bidirectional"))
    )
    (net (code "33") (name "B14_L18_P") (class "Default")
      (node (ref "JM2") (pin "87") (pinfunction "87_87") (pintype "bidirectional"))
    )
    (net (code "34") (name "B14_L19_N") (class "Default")
      (node (ref "JM2") (pin "94") (pinfunction "94_94") (pintype "bidirectional"))
    )
    (net (code "35") (name "B14_L19_P") (class "Default")
      (node (ref "JM2") (pin "92") (pinfunction "92_92") (pintype "bidirectional"))
    )
    (net (code "36") (name "B14_L20_N") (class "Default")
      (node (ref "JM2") (pin "95") (pinfunction "95_95") (pintype "bidirectional"))
    )
    (net (code "37") (name "B14_L20_P") (class "Default")
      (node (ref "JM2") (pin "93") (pinfunction "93_93") (pintype "bidirectional"))
    )
    (net (code "38") (name "B14_L21_N") (class "Default")
      (node (ref "JM1") (pin "95") (pinfunction "95_95") (pintype "bidirectional"))
    )
    (net (code "39") (name "B14_L21_P") (class "Default")
      (node (ref "JM1") (pin "93") (pinfunction "93_93") (pintype "bidirectional"))
    )
    (net (code "40") (name "B14_L22_N") (class "Default")
      (node (ref "JM2") (pin "96") (pinfunction "96_96") (pintype "bidirectional"))
    )
    (net (code "41") (name "B14_L22_P") (class "Default")
      (node (ref "JM2") (pin "98") (pinfunction "98_98") (pintype "bidirectional"))
    )
    (net (code "42") (name "B14_L23_N") (class "Default")
      (node (ref "JM1") (pin "89") (pinfunction "89_89") (pintype "bidirectional"))
    )
    (net (code "43") (name "B14_L23_P") (class "Default")
      (node (ref "JM1") (pin "91") (pinfunction "91_91") (pintype "bidirectional"))
    )
    (net (code "44") (name "B14_L24_N") (class "Default")
      (node (ref "JM1") (pin "85") (pinfunction "85_85") (pintype "bidirectional"))
    )
    (net (code "45") (name "B14_L24_P") (class "Default")
      (node (ref "JM1") (pin "87") (pinfunction "87_87") (pintype "bidirectional"))
    )
    (net (code "46") (name "B14_L25") (class "Default")
      (node (ref "JM2") (pin "97") (pinfunction "97_97") (pintype "bidirectional"))
    )
    (net (code "47") (name "B15_L1_N") (class "Default")
      (node (ref "JM2") (pin "14") (pinfunction "14_14") (pintype "bidirectional"))
    )
    (net (code "48") (name "B15_L1_P") (class "Default")
      (node (ref "JM2") (pin "16") (pinfunction "16_16") (pintype "bidirectional"))
    )
    (net (code "49") (name "B15_L2_N") (class "Default")
      (node (ref "JM2") (pin "20") (pinfunction "20_20") (pintype "bidirectional"))
    )
    (net (code "50") (name "B15_L2_P") (class "Default")
      (node (ref "JM2") (pin "22") (pinfunction "22_22") (pintype "bidirectional"))
    )
    (net (code "51") (name "B15_L3_N") (class "Default")
      (node (ref "JM2") (pin "4") (pinfunction "4_4") (pintype "bidirectional"))
    )
    (net (code "52") (name "B15_L3_P") (class "Default")
      (node (ref "JM2") (pin "2") (pinfunction "2_2") (pintype "bidirectional"))
    )
    (net (code "53") (name "B15_L4_N") (class "Default")
      (node (ref "JM2") (pin "10") (pinfunction "10_10") (pintype "bidirectional"))
    )
    (net (code "54") (name "B15_L4_P") (class "Default")
      (node (ref "JM2") (pin "12") (pinfunction "12_12") (pintype "bidirectional"))
    )
    (net (code "55") (name "B15_L5_N") (class "Default")
      (node (ref "JM2") (pin "8") (pinfunction "8_8") (pintype "bidirectional"))
    )
    (net (code "56") (name "B15_L5_P") (class "Default")
      (node (ref "JM2") (pin "6") (pinfunction "6_6") (pintype "bidirectional"))
    )
    (net (code "57") (name "B15_L6_N") (class "Default")
      (node (ref "JM2") (pin "26") (pinfunction "26_26") (pintype "bidirectional"))
    )
    (net (code "58") (name "B15_L6_P") (class "Default")
      (node (ref "JM2") (pin "24") (pinfunction "24_24") (pintype "bidirectional"))
    )
    (net (code "59") (name "B15_L7_N") (class "Default")
      (node (ref "JM2") (pin "1") (pinfunction "1_1") (pintype "bidirectional"))
    )
    (net (code "60") (name "B15_L7_P") (class "Default")
      (node (ref "JM2") (pin "3") (pinfunction "3_3") (pintype "bidirectional"))
    )
    (net (code "61") (name "B15_L8_N") (class "Default")
      (node (ref "JM2") (pin "7") (pinfunction "7_7") (pintype "bidirectional"))
    )
    (net (code "62") (name "B15_L8_P") (class "Default")
      (node (ref "JM2") (pin "5") (pinfunction "5_5") (pintype "bidirectional"))
    )
    (net (code "63") (name "B15_L9_N") (class "Default")
      (node (ref "JM2") (pin "15") (pinfunction "15_15") (pintype "bidirectional"))
    )
    (net (code "64") (name "B15_L9_P") (class "Default")
      (node (ref "JM2") (pin "13") (pinfunction "13_13") (pintype "bidirectional"))
    )
    (net (code "65") (name "B15_L10_N") (class "Default")
      (node (ref "JM2") (pin "11") (pinfunction "11_11") (pintype "bidirectional"))
    )
    (net (code "66") (name "B15_L10_P") (class "Default")
      (node (ref "JM2") (pin "9") (pinfunction "9_9") (pintype "bidirectional"))
    )
    (net (code "67") (name "B15_L11_N") (class "Default")
      (node (ref "JM2") (pin "30") (pinfunction "30_30") (pintype "bidirectional"))
    )
    (net (code "68") (name "B15_L11_P") (class "Default")
      (node (ref "JM2") (pin "28") (pinfunction "28_28") (pintype "bidirectional"))
    )
    (net (code "69") (name "B15_L12_N") (class "Default")
      (node (ref "JM2") (pin "34") (pinfunction "34_34") (pintype "bidirectional"))
    )
    (net (code "70") (name "B15_L12_P") (class "Default")
      (node (ref "JM2") (pin "32") (pinfunction "32_32") (pintype "bidirectional"))
    )
    (net (code "71") (name "B15_L13_N") (class "Default")
      (node (ref "JM2") (pin "38") (pinfunction "38_38") (pintype "bidirectional"))
    )
    (net (code "72") (name "B15_L13_P") (class "Default")
      (node (ref "JM2") (pin "40") (pinfunction "40_40") (pintype "bidirectional"))
    )
    (net (code "73") (name "B15_L14_N") (class "Default")
      (node (ref "JM2") (pin "42") (pinfunction "42_42") (pintype "bidirectional"))
    )
    (net (code "74") (name "B15_L14_P") (class "Default")
      (node (ref "JM2") (pin "44") (pinfunction "44_44") (pintype "bidirectional"))
    )
    (net (code "75") (name "B15_L15_N") (class "Default")
      (node (ref "JM2") (pin "19") (pinfunction "19_19") (pintype "bidirectional"))
    )
    (net (code "76") (name "B15_L15_P") (class "Default")
      (node (ref "JM2") (pin "21") (pinfunction "21_21") (pintype "bidirectional"))
    )
    (net (code "77") (name "B15_L16_N") (class "Default")
      (node (ref "JM2") (pin "23") (pinfunction "23_23") (pintype "bidirectional"))
    )
    (net (code "78") (name "B15_L16_P") (class "Default")
      (node (ref "JM2") (pin "25") (pinfunction "25_25") (pintype "bidirectional"))
    )
    (net (code "79") (name "B15_L17_N") (class "Default")
      (node (ref "JM2") (pin "31") (pinfunction "31_31") (pintype "bidirectional"))
    )
    (net (code "80") (name "B15_L17_P") (class "Default")
      (node (ref "JM2") (pin "33") (pinfunction "33_33") (pintype "bidirectional"))
    )
    (net (code "81") (name "B15_L18_N") (class "Default")
      (node (ref "JM2") (pin "27") (pinfunction "27_27") (pintype "bidirectional"))
    )
    (net (code "82") (name "B15_L18_P") (class "Default")
      (node (ref "JM2") (pin "29") (pinfunction "29_29") (pintype "bidirectional"))
    )
    (net (code "83") (name "B15_L19_N") (class "Default")
      (node (ref "JM2") (pin "41") (pinfunction "41_41") (pintype "bidirectional"))
    )
    (net (code "84") (name "B15_L19_P") (class "Default")
      (node (ref "JM2") (pin "43") (pinfunction "43_43") (pintype "bidirectional"))
    )
    (net (code "85") (name "B15_L20_N") (class "Default")
      (node (ref "JM2") (pin "50") (pinfunction "50_50") (pintype "bidirectional"))
    )
    (net (code "86") (name "B15_L20_P") (class "Default")
      (node (ref "JM2") (pin "52") (pinfunction "52_52") (pintype "bidirectional"))
    )
    (net (code "87") (name "B15_L21_N") (class "Default")
      (node (ref "JM2") (pin "45") (pinfunction "45_45") (pintype "bidirectional"))
    )
    (net (code "88") (name "B15_L21_P") (class "Default")
      (node (ref "JM2") (pin "47") (pinfunction "47_47") (pintype "bidirectional"))
    )
    (net (code "89") (name "B15_L22_N") (class "Default")
      (node (ref "JM2") (pin "46") (pinfunction "46_46") (pintype "bidirectional"))
    )
    (net (code "90") (name "B15_L22_P") (class "Default")
      (node (ref "JM2") (pin "48") (pinfunction "48_48") (pintype "bidirectional"))
    )
    (net (code "91") (name "B15_L23_N") (class "Default")
      (node (ref "JM2") (pin "51") (pinfunction "51_51") (pintype "bidirectional"))
    )
    (net (code "92") (name "B15_L23_P") (class "Default")
      (node (ref "JM2") (pin "49") (pinfunction "49_49") (pintype "bidirectional"))
    )
    (net (code "93") (name "B15_L24_N") (class "Default")
      (node (ref "JM2") (pin "37") (pinfunction "37_37") (pintype "bidirectional"))
    )
    (net (code "94") (name "B15_L24_P") (class "Default")
      (node (ref "JM2") (pin "39") (pinfunction "39_39") (pintype "bidirectional"))
    )
    (net (code "95") (name "B34_L1_N") (class "Default")
      (node (ref "JM1") (pin "37") (pinfunction "37_37") (pintype "bidirectional"))
    )
    (net (code "96") (name "B34_L1_P") (class "Default")
      (node (ref "JM1") (pin "35") (pinfunction "35_35") (pintype "bidirectional"))
    )
    (net (code "97") (name "B34_L2_N") (class "Default")
      (node (ref "JM1") (pin "33") (pinfunction "33_33") (pintype "bidirectional"))
    )
    (net (code "98") (name "B34_L2_P") (class "Default")
      (node (ref "JM1") (pin "31") (pinfunction "31_31") (pintype "bidirectional"))
    )
    (net (code "99") (name "B34_L3_N") (class "Default")
      (node (ref "JM1") (pin "42") (pinfunction "42_42") (pintype "bidirectional"))
    )
    (net (code "100") (name "B34_L3_P") (class "Default")
      (node (ref "JM1") (pin "40") (pinfunction "40_40") (pintype "bidirectional"))
    )
    (net (code "101") (name "B34_L4_N") (class "Default")
      (node (ref "JM1") (pin "41") (pinfunction "41_41") (pintype "bidirectional"))
    )
    (net (code "102") (name "B34_L4_P") (class "Default")
      (node (ref "JM1") (pin "39") (pinfunction "39_39") (pintype "bidirectional"))
    )
    (net (code "103") (name "B34_L5_N") (class "Default")
      (node (ref "JM1") (pin "45") (pinfunction "45_45") (pintype "bidirectional"))
    )
    (net (code "104") (name "B34_L5_P") (class "Default")
      (node (ref "JM1") (pin "43") (pinfunction "43_43") (pintype "bidirectional"))
    )
    (net (code "105") (name "B34_L6_N") (class "Default")
      (node (ref "JM1") (pin "34") (pinfunction "34_34") (pintype "bidirectional"))
    )
    (net (code "106") (name "B34_L6_P") (class "Default")
      (node (ref "JM1") (pin "32") (pinfunction "32_32") (pintype "bidirectional"))
    )
    (net (code "107") (name "B34_L7_N") (class "Default")
      (node (ref "JM1") (pin "38") (pinfunction "38_38") (pintype "bidirectional"))
    )
    (net (code "108") (name "B34_L7_P") (class "Default")
      (node (ref "JM1") (pin "36") (pinfunction "36_36") (pintype "bidirectional"))
    )
    (net (code "109") (name "B34_L8_N") (class "Default")
      (node (ref "JM1") (pin "52") (pinfunction "52_52") (pintype "bidirectional"))
    )
    (net (code "110") (name "B34_L8_P") (class "Default")
      (node (ref "JM1") (pin "50") (pinfunction "50_50") (pintype "bidirectional"))
    )
    (net (code "111") (name "B34_L9_N") (class "Default")
      (node (ref "JM1") (pin "46") (pinfunction "46_46") (pintype "bidirectional"))
    )
    (net (code "112") (name "B34_L9_P") (class "Default")
      (node (ref "JM1") (pin "44") (pinfunction "44_44") (pintype "bidirectional"))
    )
    (net (code "113") (name "B34_L10_N") (class "Default")
      (node (ref "JM1") (pin "51") (pinfunction "51_51") (pintype "bidirectional"))
    )
    (net (code "114") (name "B34_L10_P") (class "Default")
      (node (ref "JM1") (pin "49") (pinfunction "49_49") (pintype "bidirectional"))
    )
    (net (code "115") (name "B34_L11_N") (class "Default")
      (node (ref "JM1") (pin "53") (pinfunction "53_53") (pintype "bidirectional"))
    )
    (net (code "116") (name "B34_L11_P") (class "Default")
      (node (ref "JM1") (pin "55") (pinfunction "55_55") (pintype "bidirectional"))
    )
    (net (code "117") (name "B34_L12_N") (class "Default")
      (node (ref "JM1") (pin "57") (pinfunction "57_57") (pintype "bidirectional"))
    )
    (net (code "118") (name "B34_L12_P") (class "Default")
      (node (ref "JM1") (pin "59") (pinfunction "59_59") (pintype "bidirectional"))
    )
    (net (code "119") (name "B34_L13_N") (class "Default")
      (node (ref "JM1") (pin "56") (pinfunction "56_56") (pintype "bidirectional"))
    )
    (net (code "120") (name "B34_L13_P") (class "Default")
      (node (ref "JM1") (pin "54") (pinfunction "54_54") (pintype "bidirectional"))
    )
    (net (code "121") (name "B34_L14_N") (class "Default")
      (node (ref "JM1") (pin "60") (pinfunction "60_60") (pintype "bidirectional"))
    )
    (net (code "122") (name "B34_L14_P") (class "Default")
      (node (ref "JM1") (pin "58") (pinfunction "58_58") (pintype "bidirectional"))
    )
    (net (code "123") (name "B34_L15_N") (class "Default")
      (node (ref "JM1") (pin "62") (pinfunction "62_62") (pintype "bidirectional"))
    )
    (net (code "124") (name "B34_L15_P") (class "Default")
      (node (ref "JM1") (pin "64") (pinfunction "64_64") (pintype "bidirectional"))
    )
    (net (code "125") (name "B34_L16_N") (class "Default")
      (node (ref "JM1") (pin "68") (pinfunction "68_68") (pintype "bidirectional"))
    )
    (net (code "126") (name "B34_L16_P") (class "Default")
      (node (ref "JM1") (pin "70") (pinfunction "70_70") (pintype "bidirectional"))
    )
    (net (code "127") (name "B34_L17_N") (class "Default")
      (node (ref "JM1") (pin "63") (pinfunction "63_63") (pintype "bidirectional"))
    )
    (net (code "128") (name "B34_L17_P") (class "Default")
      (node (ref "JM1") (pin "65") (pinfunction "65_65") (pintype "bidirectional"))
    )
    (net (code "129") (name "B34_L18_N") (class "Default")
      (node (ref "JM1") (pin "74") (pinfunction "74_74") (pintype "bidirectional"))
    )
    (net (code "130") (name "B34_L18_P") (class "Default")
      (node (ref "JM1") (pin "72") (pinfunction "72_72") (pintype "bidirectional"))
    )
    (net (code "131") (name "B34_L19_N") (class "Default")
      (node (ref "JM1") (pin "71") (pinfunction "71_71") (pintype "bidirectional"))
    )
    (net (code "132") (name "B34_L19_P") (class "Default")
      (node (ref "JM1") (pin "73") (pinfunction "73_73") (pintype "bidirectional"))
    )
    (net (code "133") (name "B34_L20_N") (class "Default")
      (node (ref "JM1") (pin "76") (pinfunction "76_76") (pintype "bidirectional"))
      (node (ref "R4") (pin "1") (pinfunction "1_1") (pintype "passive"))
    )
    (net (code "134") (name "B34_L20_P") (class "Default")
      (node (ref "JM1") (pin "78") (pinfunction "78_78") (pintype "bidirectional"))
      (node (ref "R5") (pin "1") (pinfunction "1_1") (pintype "passive"))
    )
    (net (code "135") (name "B34_L21_N") (class "Default")
      (node (ref "JM1") (pin "69") (pinfunction "69_69") (pintype "bidirectional"))
    )
    (net (code "136") (name "B34_L21_P") (class "Default")
      (node (ref "JM1") (pin "67") (pinfunction "67_67") (pintype "bidirectional"))
    )
    (net (code "137") (name "B34_L22_N") (class "Default")
      (node (ref "JM1") (pin "75") (pinfunction "75_75") (pintype "bidirectional"))
    )
    (net (code "138") (name "B34_L22_P") (class "Default")
      (node (ref "JM1") (pin "77") (pinfunction "77_77") (pintype "bidirectional"))
    )
    (net (code "139") (name "B34_L23_N") (class "Default")
      (node (ref "JM1") (pin "79") (pinfunction "79_79") (pintype "bidirectional"))
    )
    (net (code "140") (name "B34_L23_P") (class "Default")
      (node (ref "JM1") (pin "81") (pinfunction "81_81") (pintype "bidirectional"))
    )
    (net (code "141") (name "B34_L24_N") (class "Default")
      (node (ref "JM1") (pin "80") (pinfunction "80_80") (pintype "bidirectional"))
      (node (ref "R6") (pin "1") (pinfunction "1_1") (pintype "passive"))
    )
    (net (code "142") (name "B34_L24_P") (class "Default")
      (node (ref "JM1") (pin "82") (pinfunction "82_82") (pintype "bidirectional"))
      (node (ref "R7") (pin "1") (pinfunction "1_1") (pintype "passive"))
    )
    (net (code "143") (name "BOOTMODE") (class "Default")
      (node (ref "JM2") (pin "100") (pinfunction "100_100") (pintype "bidirectional"))
      (node (ref "JP3") (pin "1") (pinfunction "1_1") (pintype "passive"))
    )
    (net (code "144") (name "CLK0_N") (class "Default")
      (node (ref "C55") (pin "2") (pinfunction "2_2") (pintype "passive"))
    )
    (net (code "145") (name "CLK0_P") (class "Default")
      (node (ref "C54") (pin "2") (pinfunction "2_2") (pintype "passive"))
    )
    (net (code "146") (name "DONE") (class "Default")
      (node (ref "D5") (pin "A@1") (pinfunction "A_A@1") (pintype "passive"))
      (node (ref "JM1") (pin "96") (pinfunction "96_96") (pintype "bidirectional"))
      (node (ref "R3") (pin "1") (pinfunction "1_1") (pintype "passive"))
    )
    (net (code "147") (name "GND") (class "Default")
      (node (ref "C1") (pin "2") (pinfunction "2_2") (pintype "passive"))
      (node (ref "C10") (pin "2") (pinfunction "2_2") (pintype "passive"))
      (node (ref "C11") (pin "2") (pinfunction "2_2") (pintype "passive"))
      (node (ref "C12") (pin "2") (pinfunction "2_2") (pintype "passive"))
      (node (ref "C13") (pin "2") (pinfunction "2_2") (pintype "passive"))
      (node (ref "C14") (pin "2") (pinfunction "2_2") (pintype "passive"))
      (node (ref "C15") (pin "2") (pinfunction "2_2") (pintype "passive"))
      (node (ref "C16") (pin "2") (pinfunction "2_2") (pintype "passive"))
      (node (ref "C22") (pin "2") (pinfunction "2_2") (pintype "passive"))
      (node (ref "C23") (pin "2") (pinfunction "2_2") (pintype "passive"))
      (node (ref "C24") (pin "2") (pinfunction "2_2") (pintype "passive"))
      (node (ref "C25") (pin "2") (pinfunction "2_2") (pintype "passive"))
      (node (ref "C26") (pin "2") (pinfunction "2_2") (pintype "passive"))
      (node (ref "C27") (pin "2") (pinfunction "2_2") (pintype "passive"))
      (node (ref "C28") (pin "2") (pinfunction "2_2") (pintype "passive"))
      (node (ref "C29") (pin "2") (pinfunction "2_2") (pintype "passive"))
      (node (ref "C30") (pin "2") (pinfunction "2_2") (pintype "passive"))
      (node (ref "C31") (pin "2") (pinfunction "2_2") (pintype "passive"))
      (node (ref "C32") (pin "2") (pinfunction "2_2") (pintype "passive"))
      (node (ref "C33") (pin "2") (pinfunction "2_2") (pintype "passive"))
      (node (ref "C34") (pin "2") (pinfunction "2_2") (pintype "passive"))
      (node (ref "C40") (pin "2") (pinfunction "2_2") (pintype "passive"))
      (node (ref "C41") (pin "2") (pinfunction "2_2") (pintype "passive"))
      (node (ref "C42") (pin "2") (pinfunction "2_2") (pintype "passive"))
      (node (ref "C43") (pin "2") (pinfunction "2_2") (pintype "passive"))
      (node (ref "C44") (pin "2") (pinfunction "2_2") (pintype "passive"))
      (node (ref "C45") (pin "2") (pinfunction "2_2") (pintype "passive"))
      (node (ref "C46") (pin "2") (pinfunction "2_2") (pintype "passive"))
      (node (ref "C47") (pin "2") (pinfunction "2_2") (pintype "passive"))
      (node (ref "C48") (pin "2") (pinfunction "2_2") (pintype "passive"))
      (node (ref "C49") (pin "2") (pinfunction "2_2") (pintype "passive"))
      (node (ref "C5") (pin "2") (pinfunction "2_2") (pintype "passive"))
      (node (ref "C50") (pin "2") (pinfunction "2_2") (pintype "passive"))
      (node (ref "C51") (pin "2") (pinfunction "2_2") (pintype "passive"))
      (node (ref "C52") (pin "2") (pinfunction "2_2") (pintype "passive"))
      (node (ref "C53") (pin "2") (pinfunction "2_2") (pintype "passive"))
      (node (ref "C6") (pin "2") (pinfunction "2_2") (pintype "passive"))
      (node (ref "C7") (pin "2") (pinfunction "2_2") (pintype "passive"))
      (node (ref "C8") (pin "2") (pinfunction "2_2") (pintype "passive"))
      (node (ref "C9") (pin "2") (pinfunction "2_2") (pintype "passive"))
      (node (ref "D5") (pin "C@1") (pinfunction "C_C@1") (pintype "passive"))
      (node (ref "JM1") (pin "100") (pinfunction "100_100") (pintype "bidirectional"))
      (node (ref "JM1") (pin "11") (pinfunction "11_11") (pintype "bidirectional"))
      (node (ref "JM1") (pin "12") (pinfunction "12_12") (pintype "bidirectional"))
      (node (ref "JM1") (pin "17") (pinfunction "17_17") (pintype "bidirectional"))
      (node (ref "JM1") (pin "18") (pinfunction "18_18") (pintype "bidirectional"))
      (node (ref "JM1") (pin "23") (pinfunction "23_23") (pintype "bidirectional"))
      (node (ref "JM1") (pin "24") (pinfunction "24_24") (pintype "bidirectional"))
      (node (ref "JM1") (pin "29") (pinfunction "29_29") (pintype "bidirectional"))
      (node (ref "JM1") (pin "30") (pinfunction "30_30") (pintype "bidirectional"))
      (node (ref "JM1") (pin "47") (pinfunction "47_47") (pintype "bidirectional"))
      (node (ref "JM1") (pin "48") (pinfunction "48_48") (pintype "bidirectional"))
      (node (ref "JM1") (pin "5") (pinfunction "5_5") (pintype "bidirectional"))
      (node (ref "JM1") (pin "6") (pinfunction "6_6") (pintype "bidirectional"))
      (node (ref "JM1") (pin "66") (pinfunction "66_66") (pintype "bidirectional"))
      (node (ref "JM1") (pin "84") (pinfunction "84_84") (pintype "bidirectional"))
      (node (ref "JM1") (pin "98") (pinfunction "98_98") (pintype "bidirectional"))
      (node (ref "JM1") (pin "F1") (pinfunction "F1_F1") (pintype "bidirectional"))
      (node (ref "JM1") (pin "F2") (pinfunction "F2_F2") (pintype "bidirectional"))
      (node (ref "JM2") (pin "17") (pinfunction "17_17") (pintype "bidirectional"))
      (node (ref "JM2") (pin "35") (pinfunction "35_35") (pintype "bidirectional"))
      (node (ref "JM2") (pin "36") (pinfunction "36_36") (pintype "bidirectional"))
      (node (ref "JM2") (pin "72") (pinfunction "72_72") (pintype "bidirectional"))
      (node (ref "JM2") (pin "83") (pinfunction "83_83") (pintype "bidirectional"))
      (node (ref "JM2") (pin "90") (pinfunction "90_90") (pintype "bidirectional"))
      (node (ref "JM2") (pin "F1") (pinfunction "F1_F1") (pintype "bidirectional"))
      (node (ref "JM2") (pin "F2") (pinfunction "F2_F2") (pintype "bidirectional"))
      (node (ref "JP2") (pin "1") (pinfunction "1_1") (pintype "passive"))
      (node (ref "JP3") (pin "2") (pinfunction "2_2") (pintype "passive"))
      (node (ref "PCIE-NORTH") (pin "A1") (pinfunction "GND_A1") (pintype "passive"))
      (node (ref "PCIE-NORTH") (pin "A10") (pinfunction "GND_A10") (pintype "passive"))
      (node (ref "PCIE-NORTH") (pin "A12") (pinfunction "GND_A12") (pintype "passive"))
      (node (ref "PCIE-NORTH") (pin "A15") (pinfunction "GND_A15") (pintype "passive"))
      (node (ref "PCIE-NORTH") (pin "A18") (pinfunction "GND_A18") (pintype "passive"))
      (node (ref "PCIE-NORTH") (pin "A4") (pinfunction "GND_A4") (pintype "passive"))
      (node (ref "PCIE-NORTH") (pin "A7") (pinfunction "GND_A7") (pintype "passive"))
      (node (ref "PCIE-NORTH") (pin "B15") (pinfunction "GND_B15") (pintype "passive"))
      (node (ref "PCIE-NORTH") (pin "B18") (pinfunction "GND_B18") (pintype "passive"))
      (node (ref "PCIE-SOUTH") (pin "A1") (pinfunction "GND_A1") (pintype "passive"))
      (node (ref "PCIE-SOUTH") (pin "A10") (pinfunction "GND_A10") (pintype "passive"))
      (node (ref "PCIE-SOUTH") (pin "A12") (pinfunction "GND_A12") (pintype "passive"))
      (node (ref "PCIE-SOUTH") (pin "A15") (pinfunction "GND_A15") (pintype "passive"))
      (node (ref "PCIE-SOUTH") (pin "A18") (pinfunction "GND_A18") (pintype "passive"))
      (node (ref "PCIE-SOUTH") (pin "A4") (pinfunction "GND_A4") (pintype "passive"))
      (node (ref "PCIE-SOUTH") (pin "A7") (pinfunction "GND_A7") (pintype "passive"))
      (node (ref "PCIE-SOUTH") (pin "B15") (pinfunction "GND_B15") (pintype "passive"))
      (node (ref "PCIE-SOUTH") (pin "B18") (pinfunction "GND_B18") (pintype "passive"))
      (node (ref "R10") (pin "2") (pinfunction "2_2") (pintype "passive"))
      (node (ref "R11") (pin "2") (pinfunction "2_2") (pintype "passive"))
      (node (ref "R12") (pin "2") (pinfunction "2_2") (pintype "passive"))
      (node (ref "R13") (pin "2") (pinfunction "2_2") (pintype "passive"))
      (node (ref "R14") (pin "2") (pinfunction "2_2") (pintype "passive"))
      (node (ref "R2") (pin "2") (pinfunction "2_2") (pintype "passive"))
      (node (ref "R8") (pin "2") (pinfunction "2_2") (pintype "passive"))
      (node (ref "R9") (pin "2") (pinfunction "2_2") (pintype "passive"))
      (node (ref "U1") (pin "1") (pinfunction "A0_1") (pintype "input"))
      (node (ref "U1") (pin "2") (pinfunction "A1_2") (pintype "input"))
      (node (ref "U1") (pin "3") (pinfunction "A2_3") (pintype "input"))
      (node (ref "U1") (pin "4") (pinfunction "GND_4") (pintype "passive"))
      (node (ref "U1") (pin "EP") (pinfunction "EP_EP") (pintype "passive"))
      (node (ref "U2") (pin "1") (pinfunction "VEE_SDI_1") (pintype "power_in"))
      (node (ref "U2") (pin "14") (pinfunction "VSS_14") (pintype "power_in"))
      (node (ref "U2") (pin "15") (pinfunction "VSS_15") (pintype "power_in"))
      (node (ref "U2") (pin "19") (pinfunction "VEE_CORE_19") (pintype "power_in"))
      (node (ref "U2") (pin "21") (pinfunction "VEEO_21") (pintype "power_in"))
      (node (ref "U2") (pin "28") (pinfunction "VEEO_28") (pintype "power_in"))
      (node (ref "U2") (pin "31") (pinfunction "VEE_CORE_31") (pintype "power_in"))
      (node (ref "U2") (pin "37") (pinfunction "VEE_CORE_37") (pintype "power_in"))
      (node (ref "U2") (pin "38") (pinfunction "VEE_CORE_38") (pintype "power_in"))
      (node (ref "U2") (pin "8") (pinfunction "VEE_SDI_8") (pintype "power_in"))
      (node (ref "U3") (pin "1") (pinfunction "VEE_DDI_1") (pintype "power_in"))
      (node (ref "U3") (pin "14") (pinfunction "VSS_14") (pintype "power_in"))
      (node (ref "U3") (pin "15") (pinfunction "VSS_15") (pintype "power_in"))
      (node (ref "U3") (pin "19") (pinfunction "VEE_CORE_19") (pintype "power_in"))
      (node (ref "U3") (pin "21") (pinfunction "VEEO_21") (pintype "power_in"))
      (node (ref "U3") (pin "28") (pinfunction "VEEO_28") (pintype "power_in"))
      (node (ref "U3") (pin "31") (pinfunction "VEE_CORE_31") (pintype "power_in"))
      (node (ref "U3") (pin "37") (pinfunction "VEE_CORE_37") (pintype "power_in"))
      (node (ref "U3") (pin "38") (pinfunction "VEE_CORE_38") (pintype "power_in"))
      (node (ref "U3") (pin "8") (pinfunction "VEE_DDI_8") (pintype "power_in"))
      (node (ref "U4") (pin "1") (pinfunction "VEE_DDI_1") (pintype "power_in"))
      (node (ref "U4") (pin "14") (pinfunction "VSS_14") (pintype "power_in"))
      (node (ref "U4") (pin "15") (pinfunction "VSS_15") (pintype "power_in"))
      (node (ref "U4") (pin "19") (pinfunction "VEE_CORE_19") (pintype "power_in"))
      (node (ref "U4") (pin "21") (pinfunction "VEEO_21") (pintype "power_in"))
      (node (ref "U4") (pin "28") (pinfunction "VEEO_28") (pintype "power_in"))
      (node (ref "U4") (pin "31") (pinfunction "VEE_CORE_31") (pintype "power_in"))
      (node (ref "U4") (pin "37") (pinfunction "VEE_CORE_37") (pintype "power_in"))
      (node (ref "U4") (pin "38") (pinfunction "VEE_CORE_38") (pintype "power_in"))
      (node (ref "U4") (pin "8") (pinfunction "VEE_DDI_8") (pintype "power_in"))
      (node (ref "U5") (pin "3") (pinfunction "GND_3") (pintype "passive"))
      (node (ref "X1") (pin "2@1") (pinfunction "GND_2@1") (pintype "passive"))
      (node (ref "X1") (pin "2@2") (pinfunction "GND_2@2") (pintype "passive"))
      (node (ref "X1") (pin "2@3") (pinfunction "GND_2@3") (pintype "passive"))
      (node (ref "X2") (pin "2@1") (pinfunction "GND_2@1") (pintype "passive"))
      (node (ref "X2") (pin "2@2") (pinfunction "GND_2@2") (pintype "passive"))
      (node (ref "X2") (pin "2@3") (pinfunction "GND_2@3") (pintype "passive"))
      (node (ref "X3") (pin "2@1") (pinfunction "GND_2@1") (pintype "passive"))
      (node (ref "X3") (pin "2@2") (pinfunction "GND_2@2") (pintype "passive"))
      (node (ref "X3") (pin "2@3") (pinfunction "GND_2@3") (pintype "passive"))
    )
    (net (code "148") (name "I2C_V") (class "Default")
      (node (ref "C1") (pin "1") (pinfunction "1_1") (pintype "passive"))
      (node (ref "PCIE-NORTH") (pin "B3") (pinfunction "V_I2C_B3") (pintype "passive"))
      (node (ref "R1") (pin "1") (pinfunction "1_1") (pintype "passive"))
      (node (ref "U1") (pin "8") (pinfunction "VCC_8") (pintype "power_in"))
    )
    (net (code "149") (name "MGT_CLK0_N") (class "Default")
      (node (ref "JM1") (pin "4") (pinfunction "4_4") (pintype "bidirectional"))
    )
    (net (code "150") (name "MGT_CLK0_P") (class "Default")
      (node (ref "JM1") (pin "2") (pinfunction "2_2") (pintype "bidirectional"))
    )
    (net (code "151") (name "MGT_RX0_N") (class "Default")
      (node (ref "JM1") (pin "21") (pinfunction "21_21") (pintype "bidirectional"))
      (node (ref "U2") (pin "27") (pinfunction "DDO0_27") (pintype "output"))
    )
    (net (code "152") (name "MGT_RX0_P") (class "Default")
      (node (ref "JM1") (pin "19") (pinfunction "19_19") (pintype "bidirectional"))
      (node (ref "U2") (pin "26") (pinfunction "~{DDO0}_26") (pintype "output"))
    )
    (net (code "153") (name "MGT_RX1_N") (class "Default")
      (node (ref "JM1") (pin "15") (pinfunction "15_15") (pintype "bidirectional"))
      (node (ref "U2") (pin "23") (pinfunction "DDO1/RCO_23") (pintype "output"))
    )
    (net (code "154") (name "MGT_RX1_P") (class "Default")
      (node (ref "JM1") (pin "13") (pinfunction "13_13") (pintype "bidirectional"))
      (node (ref "U2") (pin "22") (pinfunction "~{DDO1}/~{RCO}_22") (pintype "output"))
    )
    (net (code "155") (name "MGT_RX2_N") (class "Default")
      (node (ref "JM1") (pin "9") (pinfunction "9_9") (pintype "bidirectional"))
    )
    (net (code "156") (name "MGT_RX2_P") (class "Default")
      (node (ref "JM1") (pin "7") (pinfunction "7_7") (pintype "bidirectional"))
    )
    (net (code "157") (name "MGT_RX3_N") (class "Default")
      (node (ref "JM1") (pin "3") (pinfunction "3_3") (pintype "bidirectional"))
    )
    (net (code "158") (name "MGT_RX3_P") (class "Default")
      (node (ref "JM1") (pin "1") (pinfunction "1_1") (pintype "bidirectional"))
    )
    (net (code "159") (name "MGT_TX0_N") (class "Default")
      (node (ref "JM1") (pin "28") (pinfunction "28_28") (pintype "bidirectional"))
      (node (ref "U4") (pin "6") (pinfunction "DDI_6") (pintype "input"))
    )
    (net (code "160") (name "MGT_TX0_P") (class "Default")
      (node (ref "JM1") (pin "26") (pinfunction "26_26") (pintype "bidirectional"))
      (node (ref "U4") (pin "7") (pinfunction "~{DDI}_7") (pintype "input"))
    )
    (net (code "161") (name "MGT_TX1_N") (class "Default")
      (node (ref "JM1") (pin "22") (pinfunction "22_22") (pintype "bidirectional"))
      (node (ref "U3") (pin "6") (pinfunction "DDI_6") (pintype "input"))
    )
    (net (code "162") (name "MGT_TX1_P") (class "Default")
      (node (ref "JM1") (pin "20") (pinfunction "20_20") (pintype "bidirectional"))
      (node (ref "U3") (pin "7") (pinfunction "~{DDI}_7") (pintype "input"))
    )
    (net (code "163") (name "MGT_TX2_N") (class "Default")
      (node (ref "JM1") (pin "16") (pinfunction "16_16") (pintype "bidirectional"))
    )
    (net (code "164") (name "MGT_TX2_P") (class "Default")
      (node (ref "JM1") (pin "14") (pinfunction "14_14") (pintype "bidirectional"))
    )
    (net (code "165") (name "MGT_TX3_N") (class "Default")
      (node (ref "JM1") (pin "10") (pinfunction "10_10") (pintype "bidirectional"))
    )
    (net (code "166") (name "MGT_TX3_P") (class "Default")
      (node (ref "JM1") (pin "8") (pinfunction "8_8") (pintype "bidirectional"))
    )
    (net (code "167") (name "N$26") (class "Default")
      (node (ref "U3") (pin "17") (pinfunction "GPIO0_17") (pintype "bidirectional"))
    )
    (net (code "168") (name "N$27") (class "Default")
      (node (ref "U3") (pin "18") (pinfunction "GPIO1_18") (pintype "bidirectional"))
    )
    (net (code "169") (name "N$28") (class "Default")
      (node (ref "U3") (pin "33") (pinfunction "GPIO2_33") (pintype "bidirectional"))
    )
    (net (code "170") (name "N$29") (class "Default")
      (node (ref "U3") (pin "36") (pinfunction "GPIO3_36") (pintype "bidirectional"))
    )
    (net (code "171") (name "N$30") (class "Default")
      (node (ref "U3") (pin "12") (pinfunction "SDOUT_12") (pintype "output"))
    )
    (net (code "172") (name "N$31") (class "Default")
      (node (ref "U3") (pin "11") (pinfunction "SDIN_11") (pintype "input"))
    )
    (net (code "173") (name "N$32") (class "Default")
      (node (ref "U3") (pin "13") (pinfunction "SCLK_13") (pintype "input"))
    )
    (net (code "174") (name "N$33") (class "Default")
      (node (ref "U3") (pin "10") (pinfunction "~{CS}_10") (pintype "input"))
    )
    (net (code "175") (name "N$34") (class "Default")
      (node (ref "U3") (pin "32") (pinfunction "RCLK_32") (pintype "input"))
    )
    (net (code "176") (name "N$39") (class "Default")
      (node (ref "U2") (pin "10") (pinfunction "~{CS}_10") (pintype "input"))
    )
    (net (code "177") (name "N$40") (class "Default")
      (node (ref "U2") (pin "13") (pinfunction "SCLK_13") (pintype "input"))
    )
    (net (code "178") (name "N$41") (class "Default")
      (node (ref "U2") (pin "11") (pinfunction "SDIN_11") (pintype "input"))
    )
    (net (code "179") (name "N$42") (class "Default")
      (node (ref "U2") (pin "12") (pinfunction "SDOUT_12") (pintype "output"))
    )
    (net (code "180") (name "N$43") (class "Default")
      (node (ref "U2") (pin "17") (pinfunction "GPIO0_17") (pintype "bidirectional"))
    )
    (net (code "181") (name "N$44") (class "Default")
      (node (ref "U2") (pin "18") (pinfunction "GPIO1_18") (pintype "bidirectional"))
    )
    (net (code "182") (name "N$45") (class "Default")
      (node (ref "U2") (pin "33") (pinfunction "GPIO2_33") (pintype "bidirectional"))
    )
    (net (code "183") (name "N$46") (class "Default")
      (node (ref "U2") (pin "36") (pinfunction "GPIO3_36") (pintype "bidirectional"))
    )
    (net (code "184") (name "N$81") (class "Default")
      (node (ref "U4") (pin "32") (pinfunction "RCLK_32") (pintype "input"))
    )
    (net (code "185") (name "N$82") (class "Default")
      (node (ref "U4") (pin "10") (pinfunction "~{CS}_10") (pintype "input"))
    )
    (net (code "186") (name "N$83") (class "Default")
      (node (ref "U4") (pin "13") (pinfunction "SCLK_13") (pintype "input"))
    )
    (net (code "187") (name "N$84") (class "Default")
      (node (ref "U4") (pin "11") (pinfunction "SDIN_11") (pintype "input"))
    )
    (net (code "188") (name "N$85") (class "Default")
      (node (ref "U4") (pin "12") (pinfunction "SDOUT_12") (pintype "output"))
    )
    (net (code "189") (name "N$86") (class "Default")
      (node (ref "U4") (pin "36") (pinfunction "GPIO3_36") (pintype "bidirectional"))
    )
    (net (code "190") (name "N$87") (class "Default")
      (node (ref "U4") (pin "33") (pinfunction "GPIO2_33") (pintype "bidirectional"))
    )
    (net (code "191") (name "N$88") (class "Default")
      (node (ref "U4") (pin "18") (pinfunction "GPIO1_18") (pintype "bidirectional"))
    )
    (net (code "192") (name "N$89") (class "Default")
      (node (ref "U4") (pin "17") (pinfunction "GPIO0_17") (pintype "bidirectional"))
    )
    (net (code "193") (name "N_5V") (class "Default")
      (node (ref "PCIE-NORTH") (pin "B12") (pinfunction "5V_B12") (pintype "passive"))
    )
    (net (code "194") (name "N_IO0") (class "Default")
      (node (ref "PCIE-NORTH") (pin "B4") (pinfunction "IO0_B4") (pintype "passive"))
    )
    (net (code "195") (name "N_IO1") (class "Default")
      (node (ref "PCIE-NORTH") (pin "B5") (pinfunction "IO1_B5") (pintype "passive"))
    )
    (net (code "196") (name "N_IO2") (class "Default")
      (node (ref "PCIE-NORTH") (pin "B6") (pinfunction "IO2_B6") (pintype "passive"))
    )
    (net (code "197") (name "N_IO3") (class "Default")
      (node (ref "PCIE-NORTH") (pin "B7") (pinfunction "IO3_B7") (pintype "passive"))
    )
    (net (code "198") (name "N_IO4") (class "Default")
      (node (ref "PCIE-NORTH") (pin "B8") (pinfunction "IO4_B8") (pintype "passive"))
    )
    (net (code "199") (name "N_IO5") (class "Default")
      (node (ref "PCIE-NORTH") (pin "B9") (pinfunction "IO5_B9") (pintype "passive"))
    )
    (net (code "200") (name "N_IO6") (class "Default")
      (node (ref "PCIE-NORTH") (pin "B10") (pinfunction "IO6_B10") (pintype "passive"))
    )
    (net (code "201") (name "N_IO7") (class "Default")
      (node (ref "PCIE-NORTH") (pin "B11") (pinfunction "IO7_B11") (pintype "passive"))
    )
    (net (code "202") (name "N_LVDS0_N") (class "Default")
      (node (ref "PCIE-NORTH") (pin "A3") (pinfunction "LVDS_0B_A3") (pintype "passive"))
    )
    (net (code "203") (name "N_LVDS0_P") (class "Default")
      (node (ref "PCIE-NORTH") (pin "A2") (pinfunction "LVDS_0A_A2") (pintype "passive"))
    )
    (net (code "204") (name "N_LVDS1_N") (class "Default")
      (node (ref "PCIE-NORTH") (pin "A6") (pinfunction "LVDS_1B_A6") (pintype "passive"))
    )
    (net (code "205") (name "N_LVDS1_P") (class "Default")
      (node (ref "PCIE-NORTH") (pin "A5") (pinfunction "LVDS_1A_A5") (pintype "passive"))
    )
    (net (code "206") (name "N_LVDS2_N") (class "Default")
      (node (ref "PCIE-NORTH") (pin "A9") (pinfunction "LVDS_2B_A9") (pintype "passive"))
    )
    (net (code "207") (name "N_LVDS2_P") (class "Default")
      (node (ref "PCIE-NORTH") (pin "A8") (pinfunction "LVDS_2A_A8") (pintype "passive"))
    )
    (net (code "208") (name "N_LVDS3_N") (class "Default")
      (node (ref "PCIE-NORTH") (pin "A14") (pinfunction "LVDS_3B_A14") (pintype "passive"))
    )
    (net (code "209") (name "N_LVDS3_P") (class "Default")
      (node (ref "PCIE-NORTH") (pin "A13") (pinfunction "LVDS_3A_A13") (pintype "passive"))
    )
    (net (code "210") (name "N_LVDS4_N") (class "Default")
      (node (ref "PCIE-NORTH") (pin "A17") (pinfunction "LVDS_4B_A17") (pintype "passive"))
    )
    (net (code "211") (name "N_LVDS4_P") (class "Default")
      (node (ref "PCIE-NORTH") (pin "A16") (pinfunction "LVDS_4A_A16") (pintype "passive"))
    )
    (net (code "212") (name "N_LVDS5_N") (class "Default")
      (node (ref "PCIE-NORTH") (pin "B17") (pinfunction "LVDS_5B_B17") (pintype "passive"))
    )
    (net (code "213") (name "N_LVDS5_P") (class "Default")
      (node (ref "PCIE-NORTH") (pin "B16") (pinfunction "LVDS_5A_B16") (pintype "passive"))
    )
    (net (code "214") (name "N_PCIE_V") (class "Default")
      (node (ref "PCIE-NORTH") (pin "B13") (pinfunction "VCC_B13") (pintype "passive"))
    )
    (net (code "215") (name "N_VCCIO") (class "Default")
      (node (ref "PCIE-NORTH") (pin "B14") (pinfunction "VCCIO_B14") (pintype "passive"))
    )
    (net (code "216") (name "Net-(C2-Pad1)") (class "Default")
      (node (ref "C2") (pin "1") (pinfunction "1_1") (pintype "passive"))
      (node (ref "X1") (pin "1") (pinfunction "1_1") (pintype "passive"))
    )
    (net (code "217") (name "Net-(C4-Pad2)") (class "Default")
      (node (ref "C4") (pin "2") (pinfunction "2_2") (pintype "passive"))
      (node (ref "R8") (pin "1") (pinfunction "1_1") (pintype "passive"))
    )
    (net (code "218") (name "Net-(C17-Pad2)") (class "Default")
      (node (ref "C17") (pin "2") (pinfunction "2_2") (pintype "passive"))
      (node (ref "X2") (pin "1") (pinfunction "1_1") (pintype "passive"))
    )
    (net (code "219") (name "Net-(C18-Pad2)") (class "Default")
      (node (ref "C18") (pin "2") (pinfunction "2_2") (pintype "passive"))
      (node (ref "R9") (pin "1") (pinfunction "1_1") (pintype "passive"))
    )
    (net (code "220") (name "Net-(C19-Pad2)") (class "Default")
      (node (ref "C19") (pin "2") (pinfunction "2_2") (pintype "passive"))
      (node (ref "R10") (pin "1") (pinfunction "1_1") (pintype "passive"))
    )
    (net (code "221") (name "Net-(C20-Pad2)") (class "Default")
      (node (ref "C20") (pin "2") (pinfunction "2_2") (pintype "passive"))
      (node (ref "R11") (pin "1") (pinfunction "1_1") (pintype "passive"))
    )
    (net (code "222") (name "Net-(C35-Pad2)") (class "Default")
      (node (ref "C35") (pin "2") (pinfunction "2_2") (pintype "passive"))
      (node (ref "X3") (pin "1") (pinfunction "1_1") (pintype "passive"))
    )
    (net (code "223") (name "Net-(C36-Pad2)") (class "Default")
      (node (ref "C36") (pin "2") (pinfunction "2_2") (pintype "passive"))
      (node (ref "R12") (pin "1") (pinfunction "1_1") (pintype "passive"))
    )
    (net (code "224") (name "Net-(C37-Pad2)") (class "Default")
      (node (ref "C37") (pin "2") (pinfunction "2_2") (pintype "passive"))
      (node (ref "R13") (pin "1") (pinfunction "1_1") (pintype "passive"))
    )
    (net (code "225") (name "Net-(C38-Pad2)") (class "Default")
      (node (ref "C38") (pin "2") (pinfunction "2_2") (pintype "passive"))
      (node (ref "R14") (pin "1") (pinfunction "1_1") (pintype "passive"))
    )
    (net (code "226") (name "Net-(D1-C)") (class "Default")
      (node (ref "D1") (pin "C@1") (pinfunction "C_C@1") (pintype "passive"))
      (node (ref "R4") (pin "2") (pinfunction "2_2") (pintype "passive"))
    )
    (net (code "227") (name "Net-(D2-C)") (class "Default")
      (node (ref "D2") (pin "C@1") (pinfunction "C_C@1") (pintype "passive"))
      (node (ref "R5") (pin "2") (pinfunction "2_2") (pintype "passive"))
    )
    (net (code "228") (name "Net-(D3-C)") (class "Default")
      (node (ref "D3") (pin "C@1") (pinfunction "C_C@1") (pintype "passive"))
      (node (ref "R6") (pin "2") (pinfunction "2_2") (pintype "passive"))
    )
    (net (code "229") (name "Net-(D4-C)") (class "Default")
      (node (ref "D4") (pin "C@1") (pinfunction "C_C@1") (pintype "passive"))
      (node (ref "R7") (pin "2") (pinfunction "2_2") (pintype "passive"))
    )
    (net (code "230") (name "Net-(U1-WP)") (class "Default")
      (node (ref "R1") (pin "2") (pinfunction "2_2") (pintype "passive"))
      (node (ref "R2") (pin "1") (pinfunction "1_1") (pintype "passive"))
      (node (ref "U1") (pin "7") (pinfunction "WP_7") (pintype "input"))
    )
    (net (code "231") (name "Net-(U2-LF+)") (class "Default")
      (node (ref "C3") (pin "1") (pinfunction "1_1") (pintype "passive"))
      (node (ref "U2") (pin "39") (pinfunction "LF+_39") (pintype "passive"))
    )
    (net (code "232") (name "Net-(U2-LF-)") (class "Default")
      (node (ref "C3") (pin "2") (pinfunction "2_2") (pintype "passive"))
      (node (ref "U2") (pin "40") (pinfunction "LF-_40") (pintype "passive"))
    )
    (net (code "233") (name "Net-(U2-SDI)") (class "Default")
      (node (ref "C2") (pin "2") (pinfunction "2_2") (pintype "passive"))
      (node (ref "U2") (pin "2") (pinfunction "SDI_2") (pintype "input"))
    )
    (net (code "234") (name "Net-(U2-SDI_TERM)") (class "Default")
      (node (ref "C4") (pin "1") (pinfunction "1_1") (pintype "passive"))
      (node (ref "U2") (pin "3") (pinfunction "SDI_TERM_3") (pintype "passive"))
    )
    (net (code "235") (name "Net-(U2-VCO_FILT)") (class "Default")
      (node (ref "C5") (pin "1") (pinfunction "1_1") (pintype "passive"))
      (node (ref "U2") (pin "34") (pinfunction "VCO_FILT_34") (pintype "passive"))
    )
    (net (code "236") (name "Net-(U2-VCO_FILT10)") (class "Default")
      (node (ref "C6") (pin "1") (pinfunction "1_1") (pintype "passive"))
      (node (ref "U2") (pin "30") (pinfunction "VCO_FILT10_30") (pintype "passive"))
    )
    (net (code "237") (name "Net-(U3-LF+)") (class "Default")
      (node (ref "C21") (pin "1") (pinfunction "1_1") (pintype "passive"))
      (node (ref "U3") (pin "39") (pinfunction "LF+_39") (pintype "passive"))
    )
    (net (code "238") (name "Net-(U3-LF-)") (class "Default")
      (node (ref "C21") (pin "2") (pinfunction "2_2") (pintype "passive"))
      (node (ref "U3") (pin "40") (pinfunction "LF-_40") (pintype "passive"))
    )
    (net (code "239") (name "Net-(U3-SDO0)") (class "Default")
      (node (ref "C17") (pin "1") (pinfunction "1_1") (pintype "passive"))
      (node (ref "U3") (pin "27") (pinfunction "SDO0_27") (pintype "output"))
    )
    (net (code "240") (name "Net-(U3-SDO1{slash}RCO)") (class "Default")
      (node (ref "C19") (pin "1") (pinfunction "1_1") (pintype "passive"))
      (node (ref "U3") (pin "23") (pinfunction "SDO1/RCO_23") (pintype "output"))
    )
    (net (code "241") (name "Net-(U3-TERM)") (class "Default")
      (node (ref "C22") (pin "1") (pinfunction "1_1") (pintype "passive"))
      (node (ref "U3") (pin "5") (pinfunction "TERM_5") (pintype "passive"))
    )
    (net (code "242") (name "Net-(U3-VCO_FILT)") (class "Default")
      (node (ref "C23") (pin "1") (pinfunction "1_1") (pintype "passive"))
      (node (ref "U3") (pin "34") (pinfunction "VCO_FILT_34") (pintype "passive"))
    )
    (net (code "243") (name "Net-(U3-VCO_FILT10)") (class "Default")
      (node (ref "C24") (pin "1") (pinfunction "1_1") (pintype "passive"))
      (node (ref "U3") (pin "30") (pinfunction "VCO_FILT10_30") (pintype "passive"))
    )
    (net (code "244") (name "Net-(U3-~{SDO0})") (class "Default")
      (node (ref "C20") (pin "1") (pinfunction "1_1") (pintype "passive"))
      (node (ref "U3") (pin "26") (pinfunction "~{SDO0}_26") (pintype "output"))
    )
    (net (code "245") (name "Net-(U3-~{SDO1}{slash}~{RCO})") (class "Default")
      (node (ref "C18") (pin "1") (pinfunction "1_1") (pintype "passive"))
      (node (ref "U3") (pin "22") (pinfunction "~{SDO1}/~{RCO}_22") (pintype "output"))
    )
    (net (code "246") (name "Net-(U4-LF+)") (class "Default")
      (node (ref "C39") (pin "1") (pinfunction "1_1") (pintype "passive"))
      (node (ref "U4") (pin "39") (pinfunction "LF+_39") (pintype "passive"))
    )
    (net (code "247") (name "Net-(U4-LF-)") (class "Default")
      (node (ref "C39") (pin "2") (pinfunction "2_2") (pintype "passive"))
      (node (ref "U4") (pin "40") (pinfunction "LF-_40") (pintype "passive"))
    )
    (net (code "248") (name "Net-(U4-SDO0)") (class "Default")
      (node (ref "C35") (pin "1") (pinfunction "1_1") (pintype "passive"))
      (node (ref "U4") (pin "27") (pinfunction "SDO0_27") (pintype "output"))
    )
    (net (code "249") (name "Net-(U4-SDO1{slash}RCO)") (class "Default")
      (node (ref "C37") (pin "1") (pinfunction "1_1") (pintype "passive"))
      (node (ref "U4") (pin "23") (pinfunction "SDO1/RCO_23") (pintype "output"))
    )
    (net (code "250") (name "Net-(U4-TERM)") (class "Default")
      (node (ref "C40") (pin "1") (pinfunction "1_1") (pintype "passive"))
      (node (ref "U4") (pin "5") (pinfunction "TERM_5") (pintype "passive"))
    )
    (net (code "251") (name "Net-(U4-VCO_FILT)") (class "Default")
      (node (ref "C41") (pin "1") (pinfunction "1_1") (pintype "passive"))
      (node (ref "U4") (pin "34") (pinfunction "VCO_FILT_34") (pintype "passive"))
    )
    (net (code "252") (name "Net-(U4-VCO_FILT10)") (class "Default")
      (node (ref "C42") (pin "1") (pinfunction "1_1") (pintype "passive"))
      (node (ref "U4") (pin "30") (pinfunction "VCO_FILT10_30") (pintype "passive"))
    )
    (net (code "253") (name "Net-(U4-~{SDO0})") (class "Default")
      (node (ref "C38") (pin "1") (pinfunction "1_1") (pintype "passive"))
      (node (ref "U4") (pin "26") (pinfunction "~{SDO0}_26") (pintype "output"))
    )
    (net (code "254") (name "Net-(U4-~{SDO1}{slash}~{RCO})") (class "Default")
      (node (ref "C36") (pin "1") (pinfunction "1_1") (pintype "passive"))
      (node (ref "U4") (pin "22") (pinfunction "~{SDO1}/~{RCO}_22") (pintype "output"))
    )
    (net (code "255") (name "Net-(U5-OUT+)") (class "Default")
      (node (ref "C54") (pin "1") (pinfunction "1_1") (pintype "passive"))
      (node (ref "R15") (pin "1") (pinfunction "1_1") (pintype "passive"))
      (node (ref "U5") (pin "4") (pinfunction "OUT+_4") (pintype "output"))
    )
    (net (code "256") (name "Net-(U5-OUT-)") (class "Default")
      (node (ref "C55") (pin "1") (pinfunction "1_1") (pintype "passive"))
      (node (ref "R15") (pin "2") (pinfunction "2_2") (pintype "passive"))
      (node (ref "U5") (pin "5") (pinfunction "OUT-_5") (pintype "output"))
    )
    (net (code "257") (name "PROG_B") (class "Default")
      (node (ref "JM1") (pin "94") (pinfunction "94_94") (pintype "bidirectional"))
    )
    (net (code "258") (name "SCL") (class "Default")
      (node (ref "PCIE-NORTH") (pin "B2") (pinfunction "SCL_B2") (pintype "passive"))
      (node (ref "U1") (pin "6") (pinfunction "SCL_6") (pintype "input"))
    )
    (net (code "259") (name "SDA") (class "Default")
      (node (ref "PCIE-NORTH") (pin "B1") (pinfunction "SDA_B1") (pintype "passive"))
      (node (ref "U1") (pin "5") (pinfunction "SDA_5") (pintype "bidirectional"))
    )
    (net (code "260") (name "SPI-CLK") (class "Default")
      (node (ref "JM2") (pin "67") (pinfunction "67_67") (pintype "bidirectional"))
    )
    (net (code "261") (name "SPI-CS") (class "Default")
      (node (ref "JM2") (pin "69") (pinfunction "69_69") (pintype "bidirectional"))
    )
    (net (code "262") (name "SPI-DQ0") (class "Default")
      (node (ref "JM2") (pin "68") (pinfunction "68_68") (pintype "bidirectional"))
    )
    (net (code "263") (name "SPI-DQ1") (class "Default")
      (node (ref "JM2") (pin "71") (pinfunction "71_71") (pintype "bidirectional"))
    )
    (net (code "264") (name "SPI-DQ2") (class "Default")
      (node (ref "JM2") (pin "73") (pinfunction "73_73") (pintype "bidirectional"))
    )
    (net (code "265") (name "SPI-DQ3") (class "Default")
      (node (ref "JM2") (pin "70") (pinfunction "70_70") (pintype "bidirectional"))
    )
    (net (code "266") (name "S_5V") (class "Default")
      (node (ref "PCIE-SOUTH") (pin "B12") (pinfunction "5V_B12") (pintype "passive"))
    )
    (net (code "267") (name "S_IO0") (class "Default")
      (node (ref "PCIE-SOUTH") (pin "B4") (pinfunction "IO0_B4") (pintype "passive"))
    )
    (net (code "268") (name "S_IO1") (class "Default")
      (node (ref "PCIE-SOUTH") (pin "B5") (pinfunction "IO1_B5") (pintype "passive"))
    )
    (net (code "269") (name "S_IO2") (class "Default")
      (node (ref "PCIE-SOUTH") (pin "B6") (pinfunction "IO2_B6") (pintype "passive"))
    )
    (net (code "270") (name "S_IO3") (class "Default")
      (node (ref "PCIE-SOUTH") (pin "B7") (pinfunction "IO3_B7") (pintype "passive"))
    )
    (net (code "271") (name "S_IO4") (class "Default")
      (node (ref "PCIE-SOUTH") (pin "B8") (pinfunction "IO4_B8") (pintype "passive"))
    )
    (net (code "272") (name "S_IO5") (class "Default")
      (node (ref "PCIE-SOUTH") (pin "B9") (pinfunction "IO5_B9") (pintype "passive"))
    )
    (net (code "273") (name "S_IO6") (class "Default")
      (node (ref "PCIE-SOUTH") (pin "B10") (pinfunction "IO6_B10") (pintype "passive"))
    )
    (net (code "274") (name "S_IO7") (class "Default")
      (node (ref "PCIE-SOUTH") (pin "B11") (pinfunction "IO7_B11") (pintype "passive"))
    )
    (net (code "275") (name "S_LVDS0_N") (class "Default")
      (node (ref "PCIE-SOUTH") (pin "A3") (pinfunction "LVDS_0B_A3") (pintype "passive"))
    )
    (net (code "276") (name "S_LVDS0_P") (class "Default")
      (node (ref "PCIE-SOUTH") (pin "A2") (pinfunction "LVDS_0A_A2") (pintype "passive"))
    )
    (net (code "277") (name "S_LVDS1_N") (class "Default")
      (node (ref "PCIE-SOUTH") (pin "A6") (pinfunction "LVDS_1B_A6") (pintype "passive"))
    )
    (net (code "278") (name "S_LVDS1_P") (class "Default")
      (node (ref "PCIE-SOUTH") (pin "A5") (pinfunction "LVDS_1A_A5") (pintype "passive"))
    )
    (net (code "279") (name "S_LVDS2_N") (class "Default")
      (node (ref "PCIE-SOUTH") (pin "A9") (pinfunction "LVDS_2B_A9") (pintype "passive"))
    )
    (net (code "280") (name "S_LVDS2_P") (class "Default")
      (node (ref "PCIE-SOUTH") (pin "A8") (pinfunction "LVDS_2A_A8") (pintype "passive"))
    )
    (net (code "281") (name "S_LVDS3_N") (class "Default")
      (node (ref "PCIE-SOUTH") (pin "A14") (pinfunction "LVDS_3B_A14") (pintype "passive"))
    )
    (net (code "282") (name "S_LVDS3_P") (class "Default")
      (node (ref "PCIE-SOUTH") (pin "A13") (pinfunction "LVDS_3A_A13") (pintype "passive"))
    )
    (net (code "283") (name "S_LVDS4_N") (class "Default")
      (node (ref "PCIE-SOUTH") (pin "A17") (pinfunction "LVDS_4B_A17") (pintype "passive"))
    )
    (net (code "284") (name "S_LVDS4_P") (class "Default")
      (node (ref "PCIE-SOUTH") (pin "A16") (pinfunction "LVDS_4A_A16") (pintype "passive"))
    )
    (net (code "285") (name "S_LVDS5_N") (class "Default")
      (node (ref "PCIE-SOUTH") (pin "B17") (pinfunction "LVDS_5B_B17") (pintype "passive"))
    )
    (net (code "286") (name "S_LVDS5_P") (class "Default")
      (node (ref "PCIE-SOUTH") (pin "B16") (pinfunction "LVDS_5A_B16") (pintype "passive"))
    )
    (net (code "287") (name "S_PCIE_V") (class "Default")
      (node (ref "PCIE-SOUTH") (pin "B13") (pinfunction "VCC_B13") (pintype "passive"))
    )
    (net (code "288") (name "S_VCCIO") (class "Default")
      (node (ref "PCIE-SOUTH") (pin "B14") (pinfunction "VCCIO_B14") (pintype "passive"))
    )
    (net (code "289") (name "TCK") (class "Default")
      (node (ref "JM1") (pin "90") (pinfunction "90_90") (pintype "bidirectional"))
    )
    (net (code "290") (name "TDI") (class "Default")
      (node (ref "JM1") (pin "86") (pinfunction "86_86") (pintype "bidirectional"))
    )
    (net (code "291") (name "TDO") (class "Default")
      (node (ref "JM1") (pin "88") (pinfunction "88_88") (pintype "bidirectional"))
    )
    (net (code "292") (name "TMS") (class "Default")
      (node (ref "JM1") (pin "92") (pinfunction "92_92") (pintype "bidirectional"))
    )
    (net (code "293") (name "VCCIO0") (class "Default")
      (node (ref "JM2") (pin "53") (pinfunction "53_53") (pintype "bidirectional"))
    )
    (net (code "294") (name "VCCIO15") (class "Default")
      (node (ref "JM2") (pin "54") (pinfunction "54_54") (pintype "bidirectional"))
    )
    (net (code "295") (name "VCCIO34") (class "Default")
      (node (ref "JM1") (pin "61") (pinfunction "61_61") (pintype "bidirectional"))
    )
    (net (code "296") (name "VCCO_4") (class "Default")
      (node (ref "C14") (pin "1") (pinfunction "1_1") (pintype "passive"))
      (node (ref "C15") (pin "1") (pinfunction "1_1") (pintype "passive"))
      (node (ref "C16") (pin "1") (pinfunction "1_1") (pintype "passive"))
      (node (ref "FB3") (pin "2") (pinfunction "2_2") (pintype "passive"))
      (node (ref "U2") (pin "24") (pinfunction "VCCO_1_24") (pintype "power_in"))
      (node (ref "U2") (pin "25") (pinfunction "VCCO_0_25") (pintype "power_in"))
    )
    (net (code "297") (name "VCCO_8") (class "Default")
      (node (ref "C32") (pin "1") (pinfunction "1_1") (pintype "passive"))
      (node (ref "C33") (pin "1") (pinfunction "1_1") (pintype "passive"))
      (node (ref "C34") (pin "1") (pinfunction "1_1") (pintype "passive"))
      (node (ref "FB6") (pin "2") (pinfunction "2_2") (pintype "passive"))
      (node (ref "U3") (pin "24") (pinfunction "VCCO_1_24") (pintype "power_in"))
      (node (ref "U3") (pin "25") (pinfunction "VCCO_0_25") (pintype "power_in"))
    )
    (net (code "298") (name "VCCO_9") (class "Default")
      (node (ref "C50") (pin "1") (pinfunction "1_1") (pintype "passive"))
      (node (ref "C51") (pin "1") (pinfunction "1_1") (pintype "passive"))
      (node (ref "C52") (pin "1") (pinfunction "1_1") (pintype "passive"))
      (node (ref "FB9") (pin "2") (pinfunction "2_2") (pintype "passive"))
      (node (ref "U4") (pin "24") (pinfunction "VCCO_1_24") (pintype "power_in"))
      (node (ref "U4") (pin "25") (pinfunction "VCCO_0_25") (pintype "power_in"))
    )
    (net (code "299") (name "VCC_4") (class "Default")
      (node (ref "C11") (pin "1") (pinfunction "1_1") (pintype "passive"))
      (node (ref "C12") (pin "1") (pinfunction "1_1") (pintype "passive"))
      (node (ref "C13") (pin "1") (pinfunction "1_1") (pintype "passive"))
      (node (ref "FB2") (pin "2") (pinfunction "2_2") (pintype "passive"))
      (node (ref "U2") (pin "35") (pinfunction "VCC_CORE_35") (pintype "power_in"))
      (node (ref "U2") (pin "4") (pinfunction "VCC_SDI_4") (pintype "power_in"))
    )
    (net (code "300") (name "VCC_8") (class "Default")
      (node (ref "C29") (pin "1") (pinfunction "1_1") (pintype "passive"))
      (node (ref "C30") (pin "1") (pinfunction "1_1") (pintype "passive"))
      (node (ref "C31") (pin "1") (pinfunction "1_1") (pintype "passive"))
      (node (ref "FB5") (pin "2") (pinfunction "2_2") (pintype "passive"))
      (node (ref "U3") (pin "35") (pinfunction "VCC_CORE_35") (pintype "power_in"))
      (node (ref "U3") (pin "4") (pinfunction "VCC_DDI_4") (pintype "power_in"))
    )
    (net (code "301") (name "VCC_9") (class "Default")
      (node (ref "C47") (pin "1") (pinfunction "1_1") (pintype "passive"))
      (node (ref "C48") (pin "1") (pinfunction "1_1") (pintype "passive"))
      (node (ref "C49") (pin "1") (pinfunction "1_1") (pintype "passive"))
      (node (ref "FB8") (pin "2") (pinfunction "2_2") (pintype "passive"))
      (node (ref "U4") (pin "35") (pinfunction "VCC_CORE_35") (pintype "power_in"))
      (node (ref "U4") (pin "4") (pinfunction "VCC_DDI_4") (pintype "power_in"))
    )
    (net (code "302") (name "VDD_4") (class "Default")
      (node (ref "C10") (pin "1") (pinfunction "1_1") (pintype "passive"))
      (node (ref "C7") (pin "1") (pinfunction "1_1") (pintype "passive"))
      (node (ref "C8") (pin "1") (pinfunction "1_1") (pintype "passive"))
      (node (ref "C9") (pin "1") (pinfunction "1_1") (pintype "passive"))
      (node (ref "FB1") (pin "2") (pinfunction "2_2") (pintype "passive"))
      (node (ref "U2") (pin "16") (pinfunction "VDD_16") (pintype "power_in"))
      (node (ref "U2") (pin "20") (pinfunction "VCCO1V8_1_20") (pintype "power_in"))
      (node (ref "U2") (pin "29") (pinfunction "VCCO1V8_0_29") (pintype "power_in"))
    )
    (net (code "303") (name "VDD_8") (class "Default")
      (node (ref "C25") (pin "1") (pinfunction "1_1") (pintype "passive"))
      (node (ref "C26") (pin "1") (pinfunction "1_1") (pintype "passive"))
      (node (ref "C27") (pin "1") (pinfunction "1_1") (pintype "passive"))
      (node (ref "C28") (pin "1") (pinfunction "1_1") (pintype "passive"))
      (node (ref "FB4") (pin "2") (pinfunction "2_2") (pintype "passive"))
      (node (ref "U3") (pin "16") (pinfunction "VDD_16") (pintype "power_in"))
      (node (ref "U3") (pin "20") (pinfunction "VCCO1V8_1_20") (pintype "power_in"))
      (node (ref "U3") (pin "29") (pinfunction "VCCO1V8_0_29") (pintype "power_in"))
    )
    (net (code "304") (name "VDD_9") (class "Default")
      (node (ref "C43") (pin "1") (pinfunction "1_1") (pintype "passive"))
      (node (ref "C44") (pin "1") (pinfunction "1_1") (pintype "passive"))
      (node (ref "C45") (pin "1") (pinfunction "1_1") (pintype "passive"))
      (node (ref "C46") (pin "1") (pinfunction "1_1") (pintype "passive"))
      (node (ref "FB7") (pin "2") (pinfunction "2_2") (pintype "passive"))
      (node (ref "U4") (pin "16") (pinfunction "VDD_16") (pintype "power_in"))
      (node (ref "U4") (pin "20") (pinfunction "VCCO1V8_1_20") (pintype "power_in"))
      (node (ref "U4") (pin "29") (pinfunction "VCCO1V8_0_29") (pintype "power_in"))
    )
    (net (code "305") (name "VIN") (class "Default")
      (node (ref "JM1") (pin "97") (pinfunction "97_97") (pintype "bidirectional"))
      (node (ref "JM1") (pin "99") (pinfunction "99_99") (pintype "bidirectional"))
      (node (ref "JP2") (pin "2") (pinfunction "2_2") (pintype "passive"))
    )
    (net (code "306") (name "VSUP") (class "Default")
      (node (ref "JP2") (pin "3") (pinfunction "3_3") (pintype "passive"))
    )
    (net (code "307") (name "VXX") (class "Default")
      (node (ref "C53") (pin "1") (pinfunction "1_1") (pintype "passive"))
      (node (ref "L1") (pin "2") (pinfunction "2_2") (pintype "passive"))
      (node (ref "U5") (pin "6") (pinfunction "VCC_6") (pintype "power_in"))
    )
    (net (code "308") (name "unconnected-(JP1-Pad1)") (class "Default")
      (node (ref "JP1") (pin "1") (pinfunction "1_1") (pintype "passive"))
    )
    (net (code "309") (name "unconnected-(JP1-Pad2)") (class "Default")
      (node (ref "JP1") (pin "2") (pinfunction "2_2") (pintype "passive"))
    )
    (net (code "310") (name "unconnected-(JP1-Pad3)") (class "Default")
      (node (ref "JP1") (pin "3") (pinfunction "3_3") (pintype "passive"))
    )
    (net (code "311") (name "unconnected-(JP1-Pad4)") (class "Default")
      (node (ref "JP1") (pin "4") (pinfunction "4_4") (pintype "passive"))
    )
    (net (code "312") (name "unconnected-(JP1-Pad5)") (class "Default")
      (node (ref "JP1") (pin "5") (pinfunction "5_5") (pintype "passive"))
    )
    (net (code "313") (name "unconnected-(JP1-Pad6)") (class "Default")
      (node (ref "JP1") (pin "6") (pinfunction "6_6") (pintype "passive"))
    )
    (net (code "314") (name "unconnected-(JP1-Pad7)") (class "Default")
      (node (ref "JP1") (pin "7") (pinfunction "7_7") (pintype "passive"))
    )
    (net (code "315") (name "unconnected-(JP1-Pad8)") (class "Default")
      (node (ref "JP1") (pin "8") (pinfunction "8_8") (pintype "passive"))
    )
    (net (code "316") (name "unconnected-(JP1-Pad9)") (class "Default")
      (node (ref "JP1") (pin "9") (pinfunction "9_9") (pintype "passive"))
    )
    (net (code "317") (name "unconnected-(JP1-Pad10)") (class "Default")
      (node (ref "JP1") (pin "10") (pinfunction "10_10") (pintype "passive"))
    )
    (net (code "318") (name "unconnected-(JP1-Pad11)") (class "Default")
      (node (ref "JP1") (pin "11") (pinfunction "11_11") (pintype "passive"))
    )
    (net (code "319") (name "unconnected-(JP1-Pad12)") (class "Default")
      (node (ref "JP1") (pin "12") (pinfunction "12_12") (pintype "passive"))
    )
    (net (code "320") (name "unconnected-(JP1-Pad13)") (class "Default")
      (node (ref "JP1") (pin "13") (pinfunction "13_13") (pintype "passive"))
    )
    (net (code "321") (name "unconnected-(JP1-Pad14)") (class "Default")
      (node (ref "JP1") (pin "14") (pinfunction "14_14") (pintype "passive"))
    )
    (net (code "322") (name "unconnected-(PCIE-NORTH-PWRGD-PadA11)") (class "Default")
      (node (ref "PCIE-NORTH") (pin "A11") (pinfunction "PWRGD_A11") (pintype "passive"))
    )
    (net (code "323") (name "unconnected-(PCIE-SOUTH-PWRGD-PadA11)") (class "Default")
      (node (ref "PCIE-SOUTH") (pin "A11") (pinfunction "PWRGD_A11") (pintype "passive"))
    )
    (net (code "324") (name "unconnected-(PCIE-SOUTH-SCL-PadB2)") (class "Default")
      (node (ref "PCIE-SOUTH") (pin "B2") (pinfunction "SCL_B2") (pintype "passive"))
    )
    (net (code "325") (name "unconnected-(PCIE-SOUTH-SDA-PadB1)") (class "Default")
      (node (ref "PCIE-SOUTH") (pin "B1") (pinfunction "SDA_B1") (pintype "passive"))
    )
    (net (code "326") (name "unconnected-(PCIE-SOUTH-V_I2C-PadB3)") (class "Default")
      (node (ref "PCIE-SOUTH") (pin "B3") (pinfunction "V_I2C_B3") (pintype "passive"))
    )
  )
)
